# 04_-CPU_SIGNAL.net
KiCad netlist of a schematic drawn in Altium Designer
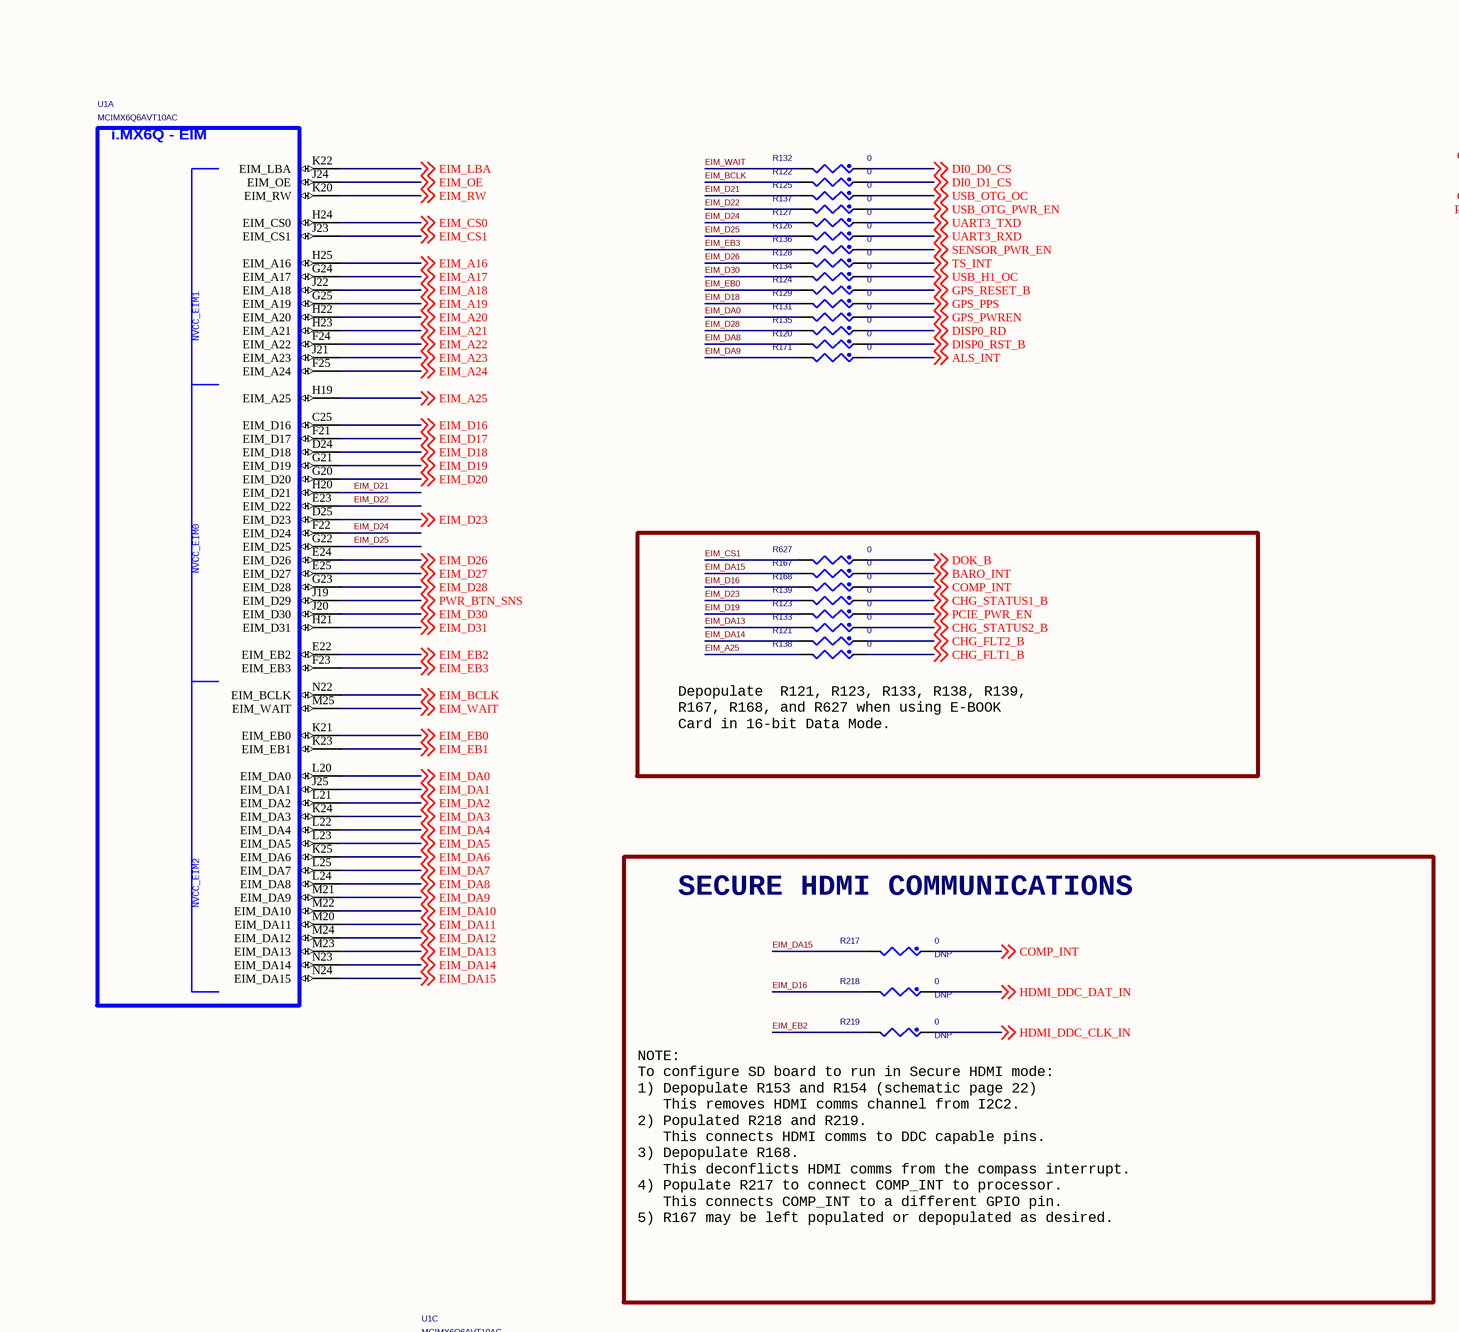
[diagram p0: [04]-CPU SIGNAL.SchDoc, top left]
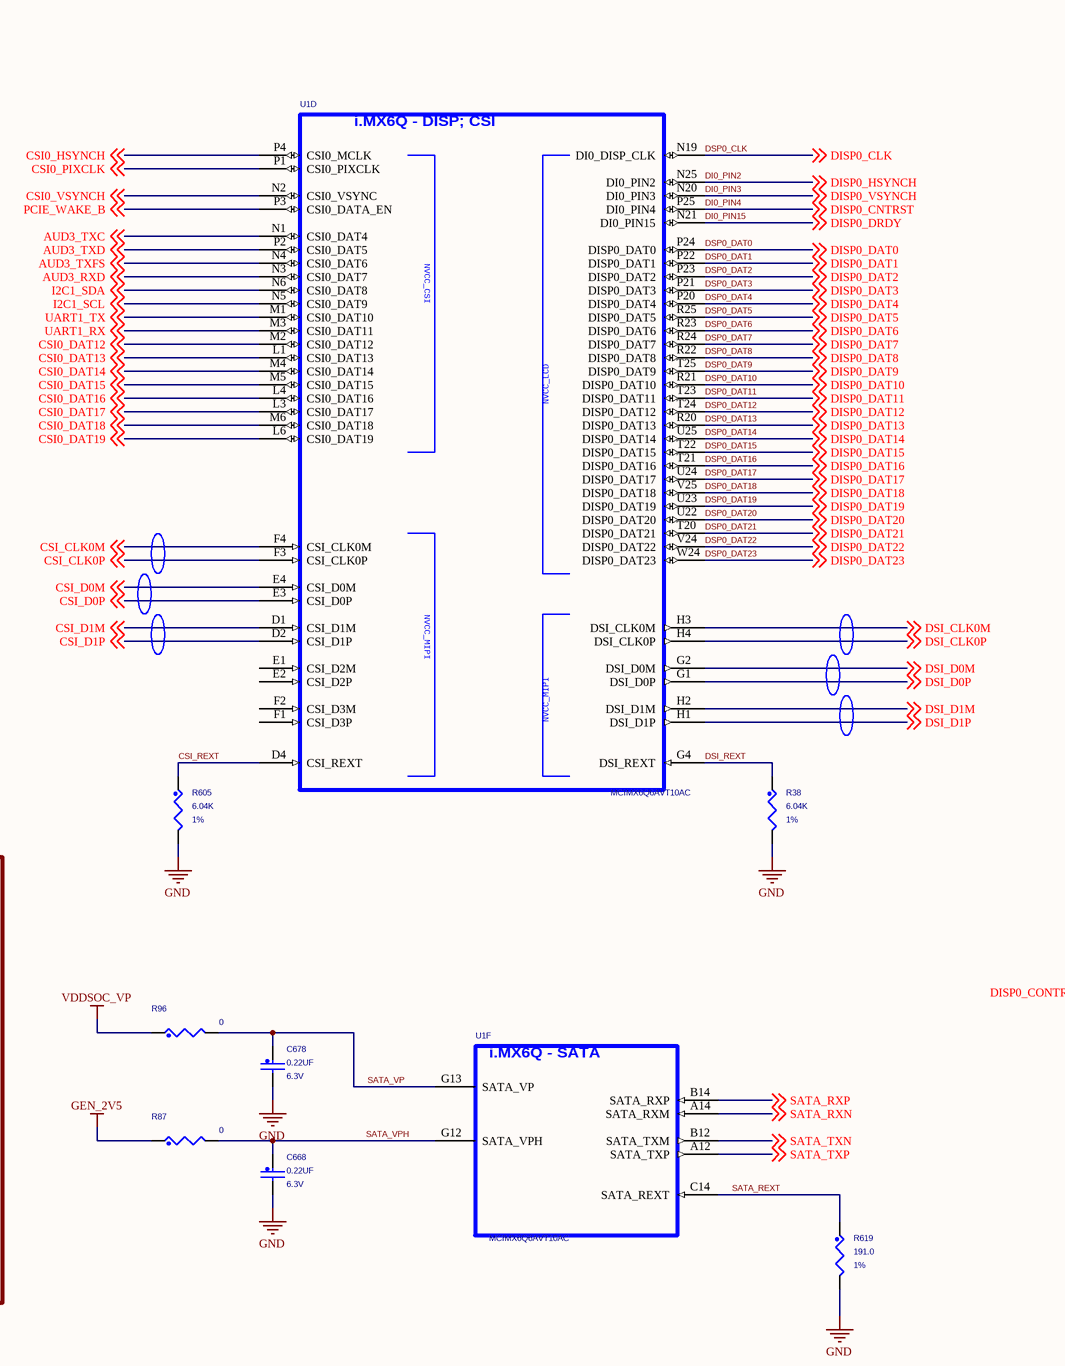
[diagram p1: [04]-CPU SIGNAL.SchDoc, top middle]
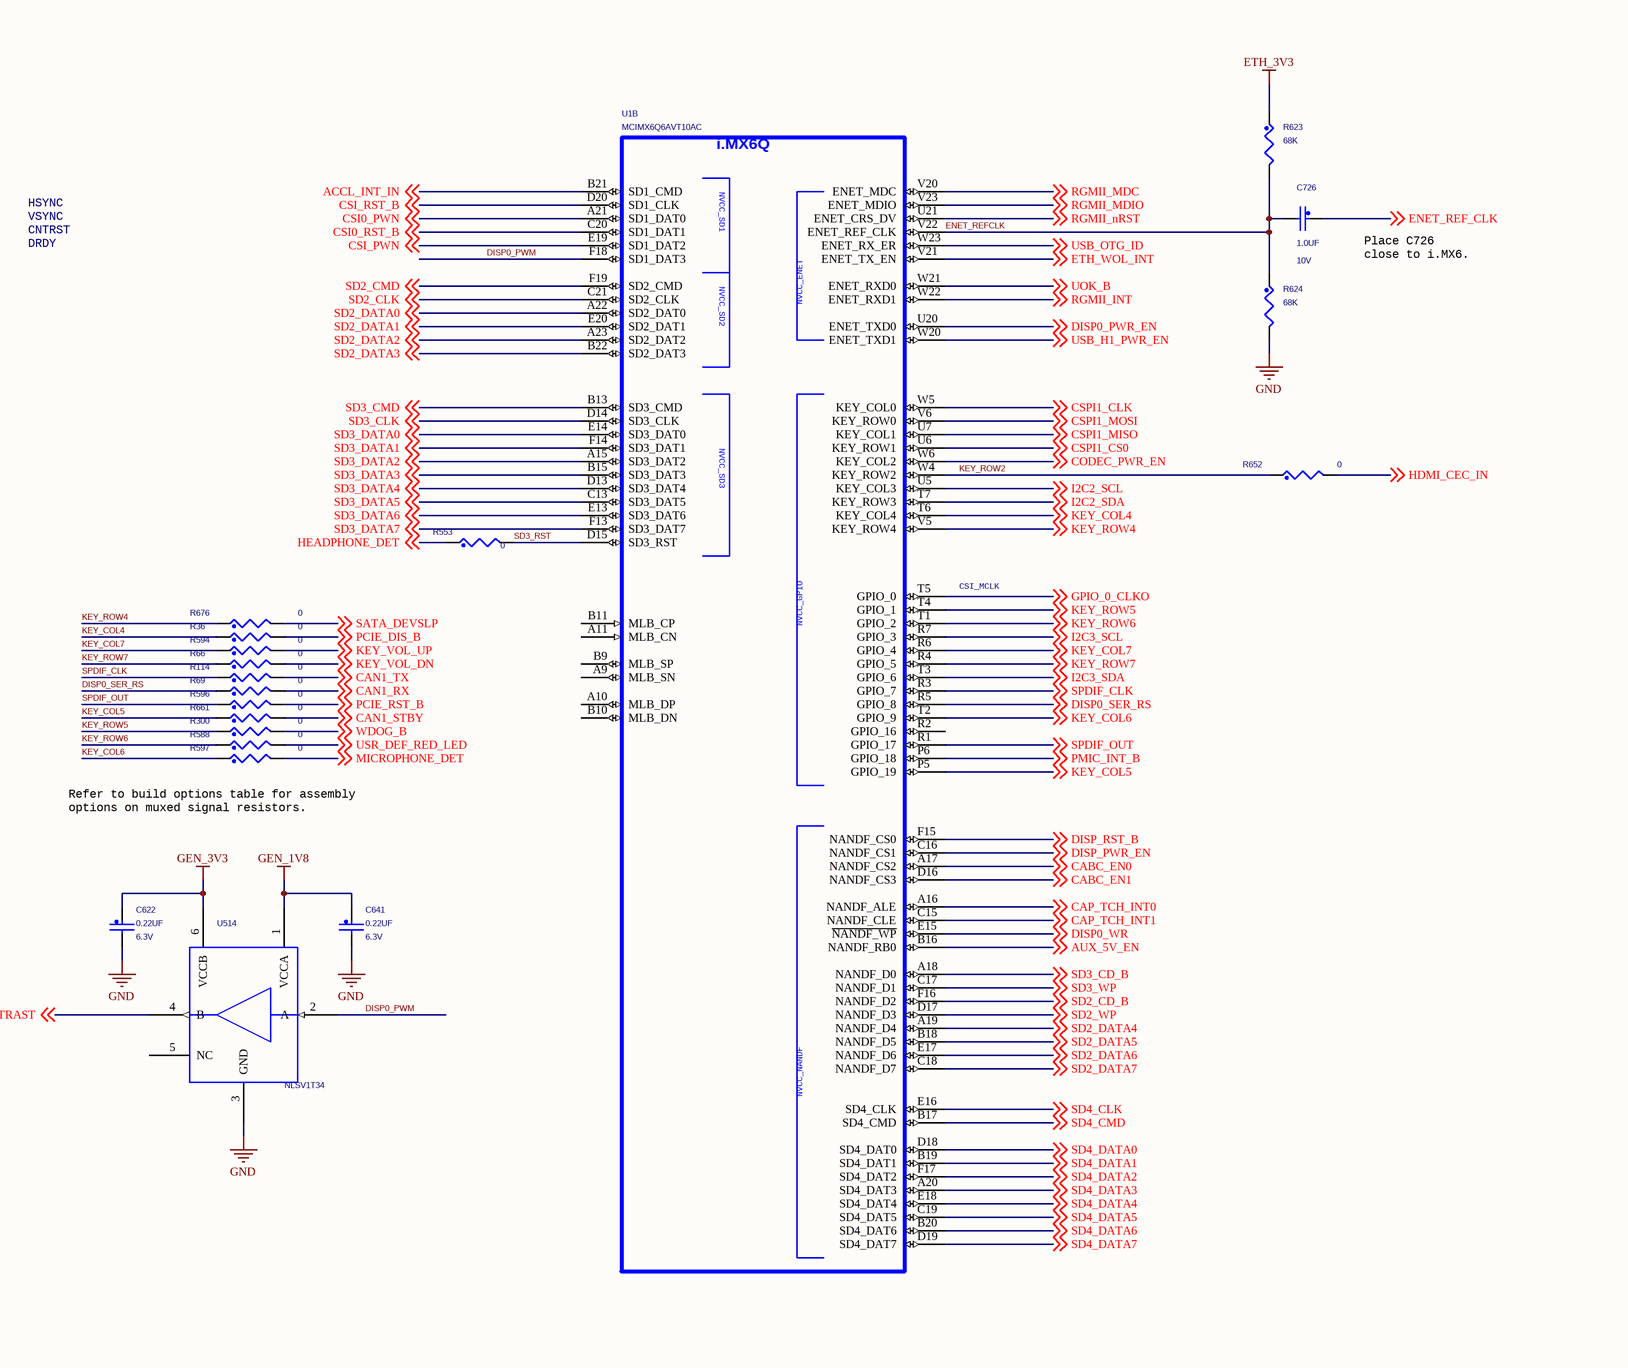
[diagram p2: [04]-CPU SIGNAL.SchDoc, top right]
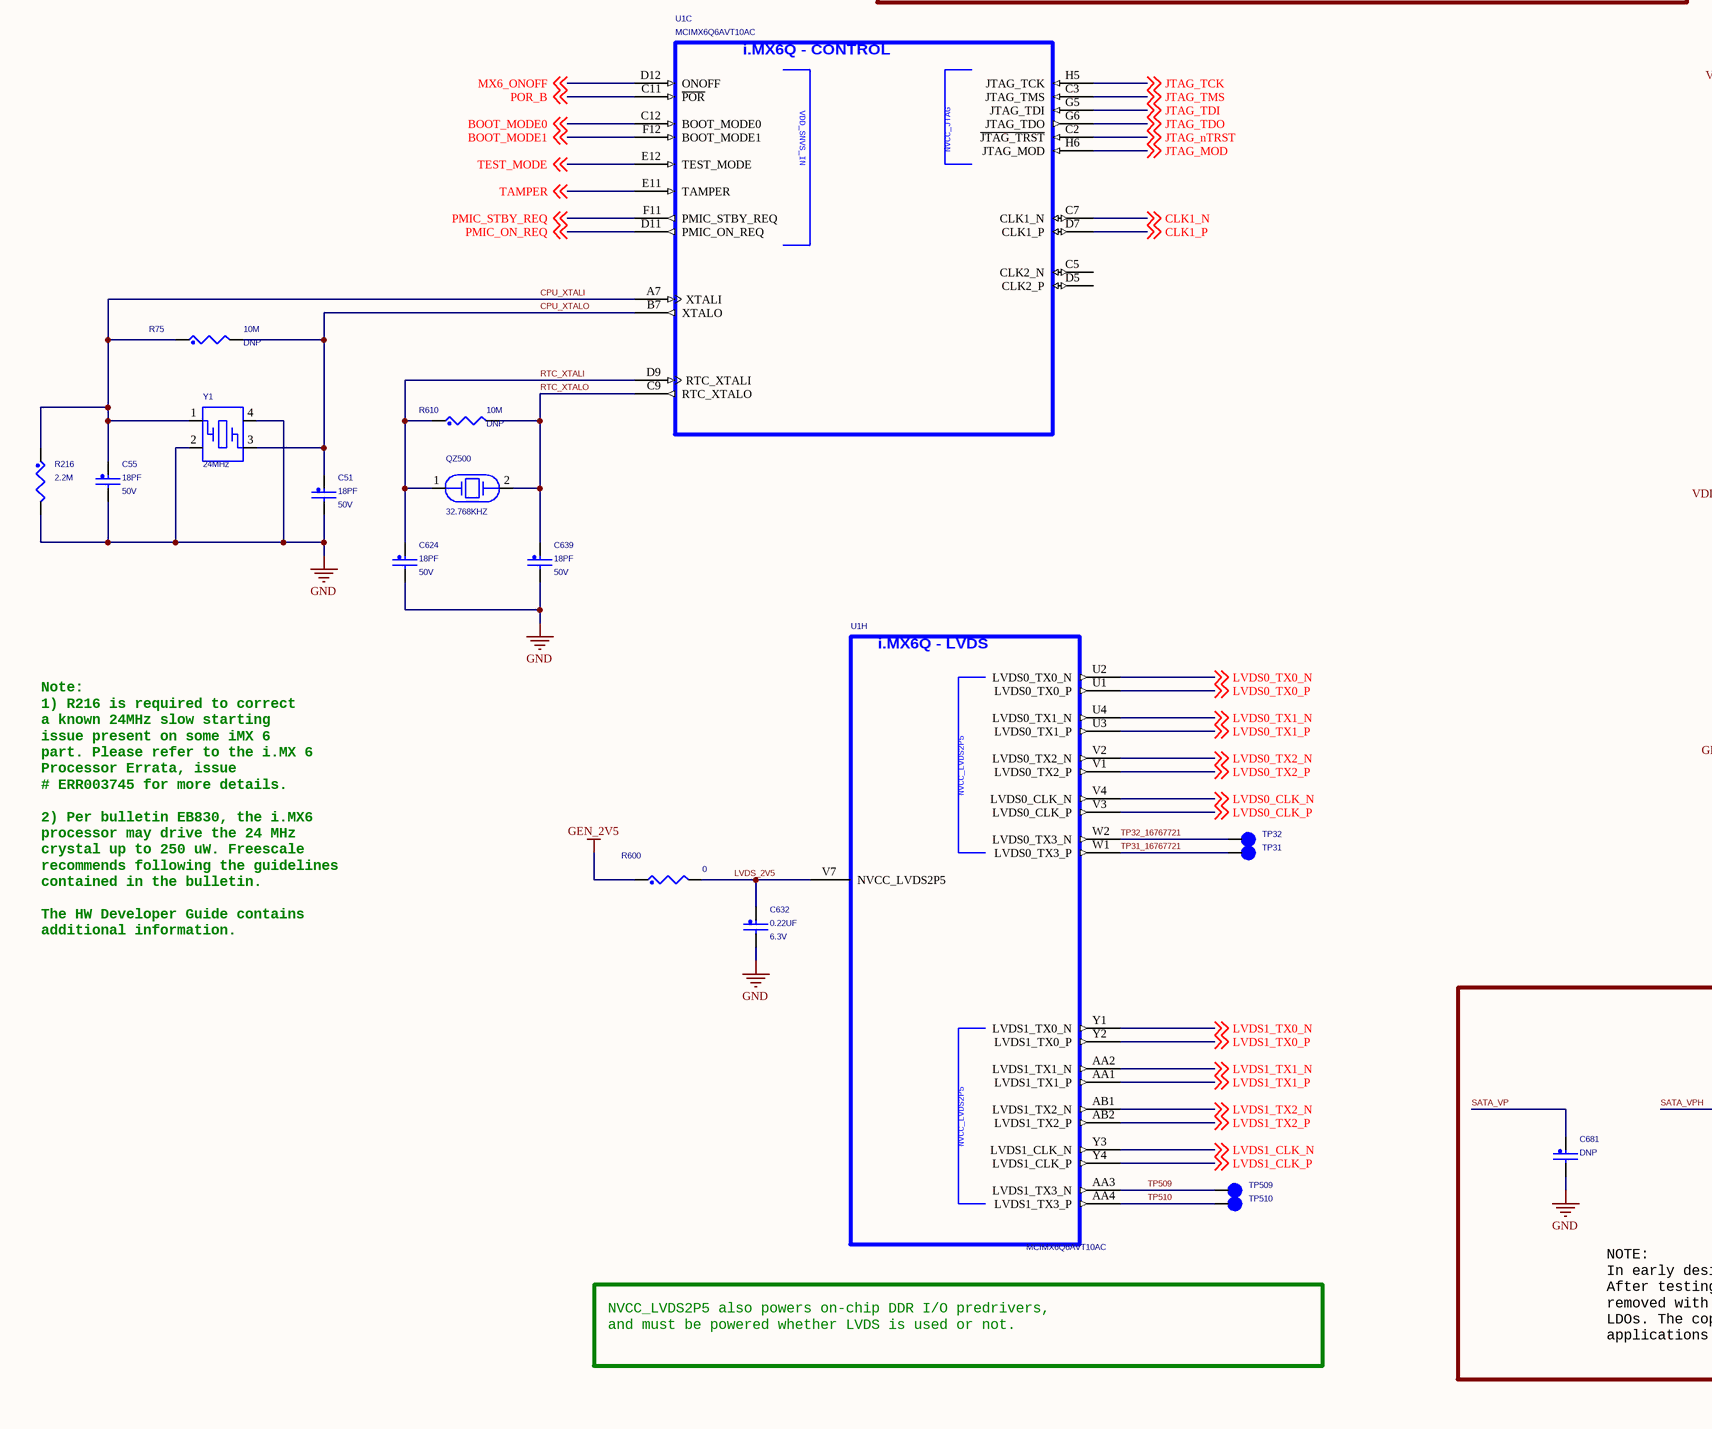
[diagram p3: [04]-CPU SIGNAL.SchDoc, bottom left]
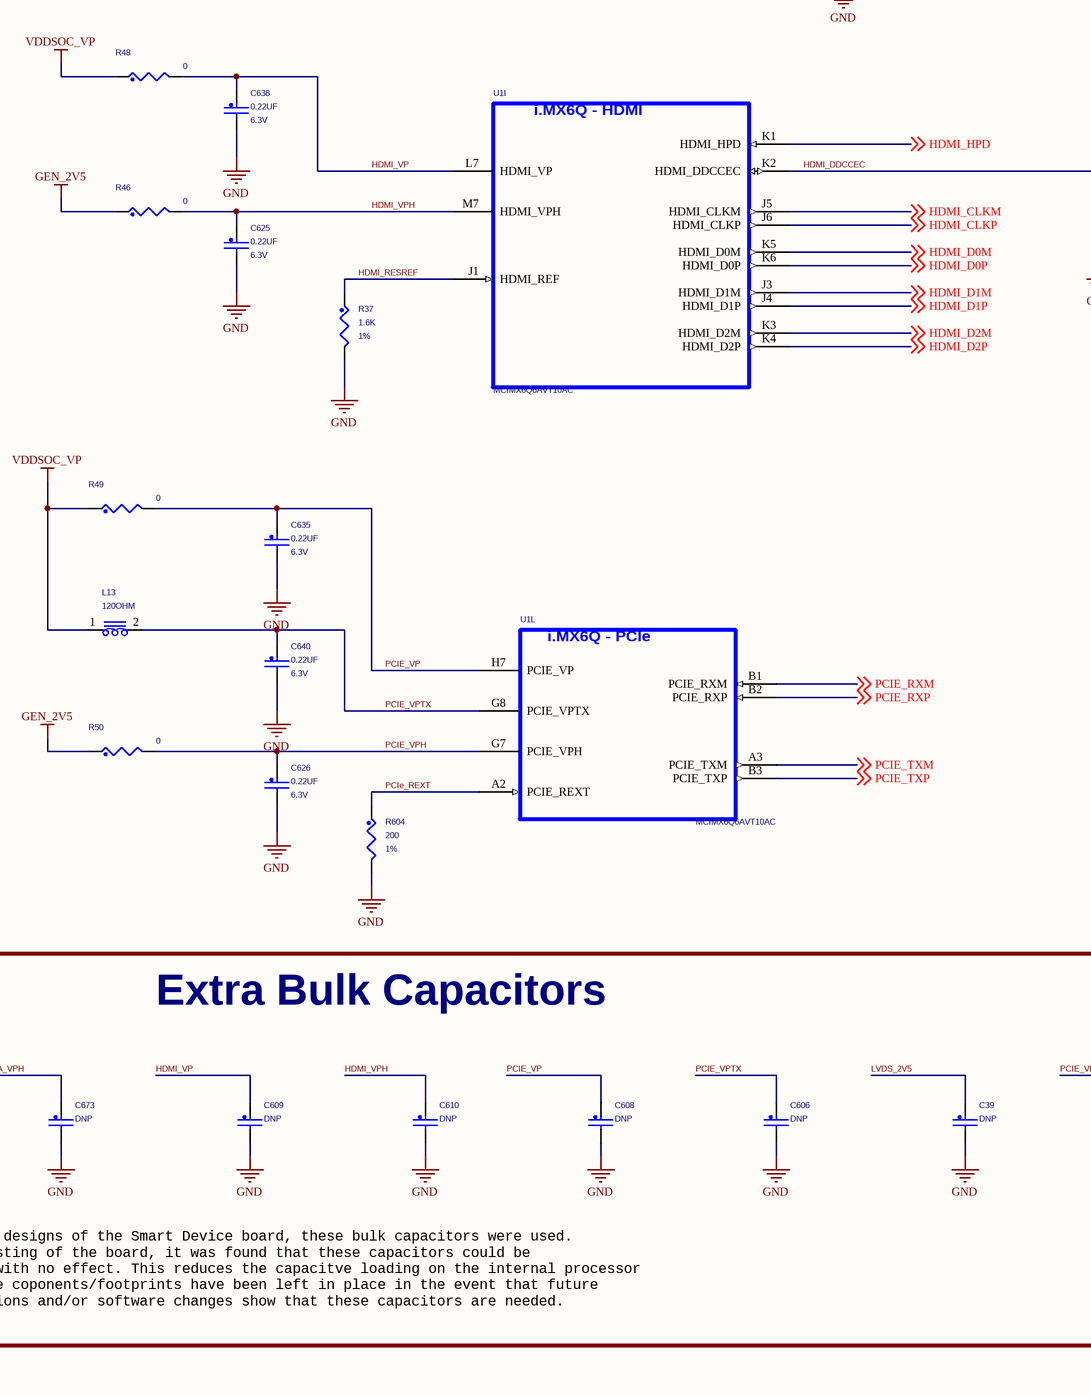
[diagram p4: [04]-CPU SIGNAL.SchDoc, bottom middle]
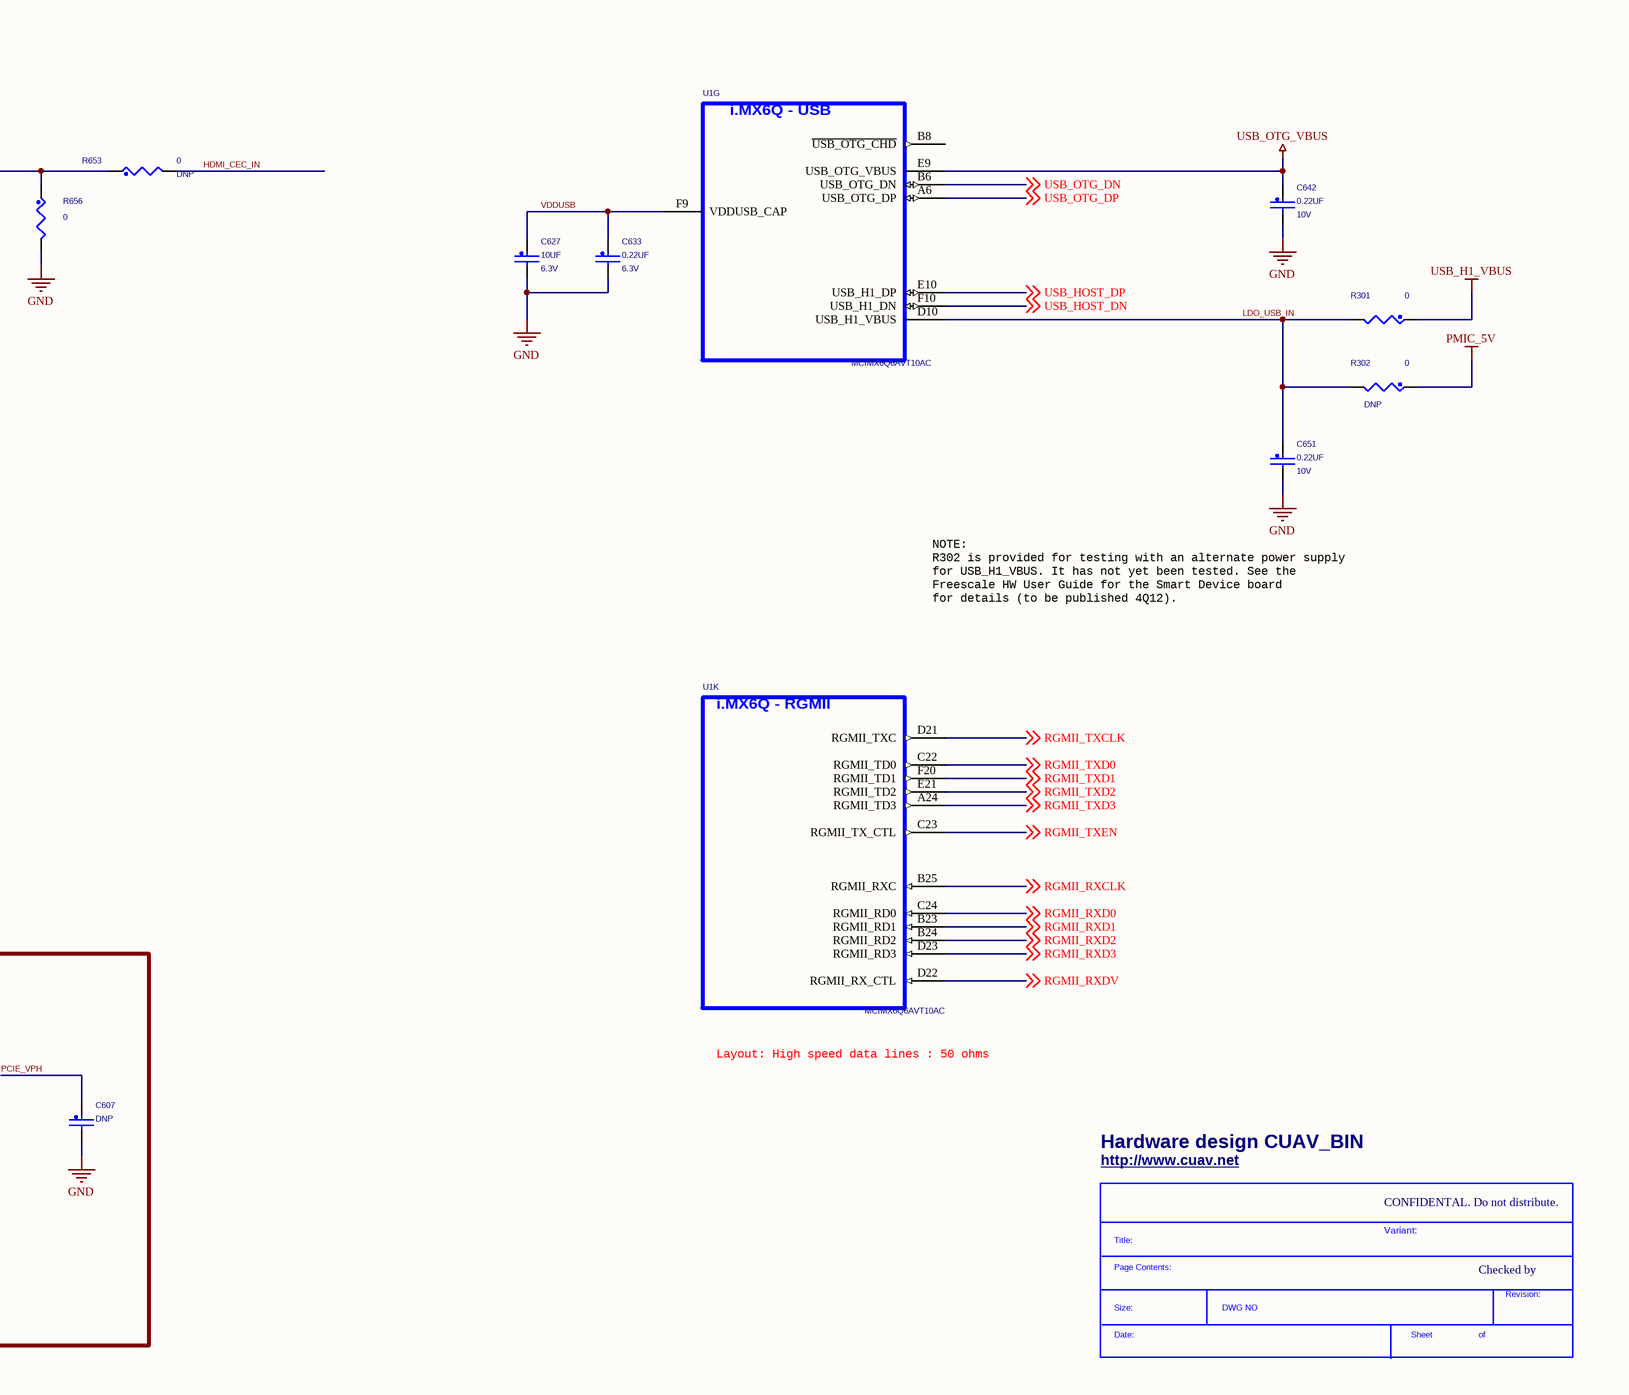
[diagram p5: [04]-CPU SIGNAL.SchDoc, bottom right]

(export (version "E")
  (design (tool "Eeschema 10.0.6"))
  (components
    (comp (ref "*") (value "SDTitleBlock") (libsource (lib "*") (part "SDTitleBlock")))
    (comp (ref "C39")
      (value "4.7UF")
      (description "CAP CER 4.7UF 10V 10% X5R 0603")
      (fields (field (name "TOLERANCE") "10%") (field (name "ASSY_OPT") "DNP") (field (name "VOLTAGE") "10V"))
      (libsource (lib "*") (part "CAP_NP"))
    )
    (comp (ref "C51")
      (value "18PF")
      (description "CAP CER 18PF 50V 1% C0G 0402")
      (fields (field (name "VOLTAGE") "50V") (field (name "TOLERANCE") "1%"))
      (libsource (lib "*") (part "CAP_NP"))
    )
    (comp (ref "C55")
      (value "18PF")
      (description "CAP CER 18PF 50V 1% C0G 0402")
      (fields (field (name "VOLTAGE") "50V") (field (name "TOLERANCE") "1%"))
      (libsource (lib "*") (part "CAP_NP"))
    )
    (comp (ref "C606")
      (value "4.7UF")
      (description "CAP CER 4.7UF 6.3V 10% X5R 0603")
      (fields
        (field (name "VOLTAGE") "6.3V")
        (field (name "TOLERANCE") "10%")
        (field (name "ASSY_OPT") "DNP")
      )
      (libsource (lib "*") (part "CAP_NP"))
    )
    (comp (ref "C607")
      (value "4.7UF")
      (description "CAP CER 4.7UF 6.3V 10% X5R 0603")
      (fields
        (field (name "VOLTAGE") "6.3V")
        (field (name "TOLERANCE") "10%")
        (field (name "ASSY_OPT") "DNP")
      )
      (libsource (lib "*") (part "CAP_NP"))
    )
    (comp (ref "C608")
      (value "4.7UF")
      (description "CAP CER 4.7UF 6.3V 10% X5R 0603")
      (fields
        (field (name "VOLTAGE") "6.3V")
        (field (name "TOLERANCE") "10%")
        (field (name "ASSY_OPT") "DNP")
      )
      (libsource (lib "*") (part "CAP_NP"))
    )
    (comp (ref "C609")
      (value "4.7UF")
      (description "CAP CER 4.7UF 6.3V 10% X5R 0603")
      (fields
        (field (name "TOLERANCE") "10%")
        (field (name "ASSY_OPT") "DNP")
        (field (name "VOLTAGE") "6.3V")
      )
      (libsource (lib "*") (part "CAP_NP"))
    )
    (comp (ref "C610")
      (value "4.7UF")
      (description "CAP CER 4.7UF 6.3V 10% X5R 0603")
      (fields
        (field (name "ASSY_OPT") "DNP")
        (field (name "TOLERANCE") "10%")
        (field (name "VOLTAGE") "6.3V")
      )
      (libsource (lib "*") (part "CAP_NP"))
    )
    (comp (ref "C622")
      (value "0.22UF")
      (description "CAP CER 0.22UF 6.3V 20% X5R 0201")
      (fields (field (name "TOLERANCE") "20%") (field (name "WVDC") "6.3V") (field (name "VOLTAGE") "6.3V"))
      (libsource (lib "*") (part "CAP_NP"))
    )
    (comp (ref "C624")
      (value "18PF")
      (description "CAP CER 18PF 50V 1% C0G 0402")
      (fields (field (name "VOLTAGE") "50V") (field (name "TOLERANCE") "1%"))
      (libsource (lib "*") (part "CAP_NP"))
    )
    (comp (ref "C625")
      (value "0.22UF")
      (description "CAP CER 0.22UF 6.3V 20% X5R 0201")
      (fields (field (name "WVDC") "6.3V") (field (name "TOLERANCE") "20%") (field (name "VOLTAGE") "6.3V"))
      (libsource (lib "*") (part "CAP_NP"))
    )
    (comp (ref "C626")
      (value "0.22UF")
      (description "CAP CER 0.22UF 6.3V 20% X5R 0201")
      (fields (field (name "VOLTAGE") "6.3V") (field (name "TOLERANCE") "20%") (field (name "WVDC") "6.3V"))
      (libsource (lib "*") (part "CAP_NP"))
    )
    (comp (ref "C627")
      (value "10UF")
      (description "CAP CER 10UF 6.3V 10% X5R 0603")
      (fields (field (name "TOLERANCE") "10%") (field (name "WVDC") "6.3V") (field (name "VOLTAGE") "6.3V"))
      (libsource (lib "*") (part "CAP_NP"))
    )
    (comp (ref "C632")
      (value "0.22UF")
      (description "CAP CER 0.22UF 6.3V 20% X5R 0201")
      (fields (field (name "VOLTAGE") "6.3V") (field (name "WVDC") "6.3V") (field (name "TOLERANCE") "20%"))
      (libsource (lib "*") (part "CAP_NP"))
    )
    (comp (ref "C633")
      (value "0.22UF")
      (description "CAP CER 0.22UF 6.3V 20% X5R 0201")
      (fields (field (name "WVDC") "6.3V") (field (name "TOLERANCE") "20%") (field (name "VOLTAGE") "6.3V"))
      (libsource (lib "*") (part "CAP_NP"))
    )
    (comp (ref "C635")
      (value "0.22UF")
      (description "CAP CER 0.22UF 6.3V 20% X5R 0201")
      (fields (field (name "VOLTAGE") "6.3V") (field (name "TOLERANCE") "20%") (field (name "WVDC") "6.3V"))
      (libsource (lib "*") (part "CAP_NP"))
    )
    (comp (ref "C638")
      (value "0.22UF")
      (description "CAP CER 0.22UF 6.3V 20% X5R 0201")
      (fields (field (name "WVDC") "6.3V") (field (name "TOLERANCE") "20%") (field (name "VOLTAGE") "6.3V"))
      (libsource (lib "*") (part "CAP_NP"))
    )
    (comp (ref "C639")
      (value "18PF")
      (description "CAP CER 18PF 50V 1% C0G 0402")
      (fields (field (name "VOLTAGE") "50V") (field (name "TOLERANCE") "1%"))
      (libsource (lib "*") (part "CAP_NP"))
    )
    (comp (ref "C640")
      (value "0.22UF")
      (description "CAP CER 0.22UF 6.3V 20% X5R 0201")
      (fields (field (name "VOLTAGE") "6.3V") (field (name "TOLERANCE") "20%") (field (name "WVDC") "6.3V"))
      (libsource (lib "*") (part "CAP_NP"))
    )
    (comp (ref "C641")
      (value "0.22UF")
      (description "CAP CER 0.22UF 6.3V 20% X5R 0201")
      (fields (field (name "VOLTAGE") "6.3V") (field (name "WVDC") "6.3V") (field (name "TOLERANCE") "20%"))
      (libsource (lib "*") (part "CAP_NP"))
    )
    (comp (ref "C642")
      (value "0.22UF")
      (description "CAP CER 0.22UF 10V 20% X5R 0201")
      (fields (field (name "WVDC") "10V") (field (name "TOLERANCE") "20%") (field (name "VOLTAGE") "10V"))
      (libsource (lib "*") (part "CAP_NP"))
    )
    (comp (ref "C651")
      (value "0.22UF")
      (description "CAP CER 0.22UF 10V 20% X5R 0201")
      (fields (field (name "WVDC") "10V") (field (name "TOLERANCE") "20%") (field (name "VOLTAGE") "10V"))
      (libsource (lib "*") (part "CAP_NP"))
    )
    (comp (ref "C668")
      (value "0.22UF")
      (description "CAP CER 0.22UF 6.3V 20% X5R 0201")
      (fields (field (name "TOLERANCE") "20%") (field (name "WVDC") "6.3V") (field (name "VOLTAGE") "6.3V"))
      (libsource (lib "*") (part "CAP_NP"))
    )
    (comp (ref "C673")
      (value "4.7UF")
      (description "CAP CER 4.7UF 6.3V 10% X5R 0603")
      (fields
        (field (name "VOLTAGE") "6.3V")
        (field (name "TOLERANCE") "10%")
        (field (name "ASSY_OPT") "DNP")
      )
      (libsource (lib "*") (part "CAP_NP"))
    )
    (comp (ref "C678")
      (value "0.22UF")
      (description "CAP CER 0.22UF 6.3V 20% X5R 0201")
      (fields (field (name "TOLERANCE") "20%") (field (name "WVDC") "6.3V") (field (name "VOLTAGE") "6.3V"))
      (libsource (lib "*") (part "CAP_NP"))
    )
    (comp (ref "C681")
      (value "4.7UF")
      (description "CAP CER 4.7UF 6.3V 10% X5R 0603")
      (fields
        (field (name "VOLTAGE") "6.3V")
        (field (name "TOLERANCE") "10%")
        (field (name "ASSY_OPT") "DNP")
      )
      (libsource (lib "*") (part "CAP_NP"))
    )
    (comp (ref "C726")
      (value "1.0UF")
      (description "CAP CER 1.0UF 10V 10% X5R 0402")
      (fields (field (name "WVDC") "10V"))
      (libsource (lib "*") (part "CAP_NP"))
    )
    (comp (ref "L13")
      (value "120OHM")
      (description "IND FER BEAD 120OHM@100MHZ 2A 25% 0603")
      (fields (field (name "TOLERANCE") "25%"))
      (libsource (lib "*") (part "BEAD_0"))
    )
    (comp (ref "QZ500")
      (value "32.768KHZ")
      (description "XTAL 32.768KHZ 12.5PF 20PPM 3.2X1.5MM SMT")
      (libsource (lib "*") (part "XTAL"))
    )
    (comp (ref "R36")
      (value "0")
      (description "RES MF ZERO OHM 1/10W -- 0402")
      (libsource (lib "*") (part "RES"))
    )
    (comp (ref "R37")
      (value "1.6K")
      (description "RES MF 1.6K  1/16W 1% 0402")
      (fields (field (name "TOLERANCE") "1%"))
      (libsource (lib "*") (part "RES"))
    )
    (comp (ref "R38")
      (value "6.04K")
      (description "RES MF 6.04K  1/16W 1% 0402")
      (fields (field (name "TOLERANCE") "1%"))
      (libsource (lib "*") (part "RES"))
    )
    (comp (ref "R46")
      (value "0")
      (description "RES MF ZERO OHM 1/10W -- 0402")
      (libsource (lib "*") (part "RES"))
    )
    (comp (ref "R48")
      (value "0")
      (description "RES MF ZERO OHM 1/10W -- 0402")
      (libsource (lib "*") (part "RES"))
    )
    (comp (ref "R49")
      (value "0")
      (description "RES MF ZERO OHM 1/10W -- 0402")
      (libsource (lib "*") (part "RES"))
    )
    (comp (ref "R50")
      (value "0")
      (description "RES MF ZERO OHM 1/10W -- 0402")
      (libsource (lib "*") (part "RES"))
    )
    (comp (ref "R66")
      (value "0")
      (description "RES MF ZERO OHM 1/10W -- 0402")
      (libsource (lib "*") (part "RES"))
    )
    (comp (ref "R69")
      (value "0")
      (description "RES MF ZERO OHM 1/10W -- 0402")
      (libsource (lib "*") (part "RES"))
    )
    (comp (ref "R75")
      (value "10M")
      (description "RES MF 10M 1/16W 1% 0402")
      (fields (field (name "ASSY_OPT") "DNP") (field (name "TOLERANCE") "1%"))
      (libsource (lib "*") (part "RES"))
    )
    (comp (ref "R87")
      (value "0")
      (description "RES MF ZERO OHM 1/10W -- 0402")
      (libsource (lib "*") (part "RES"))
    )
    (comp (ref "R96")
      (value "0")
      (description "RES MF ZERO OHM 1/10W -- 0402")
      (libsource (lib "*") (part "RES"))
    )
    (comp (ref "R114")
      (value "0")
      (description "RES MF ZERO OHM 1/10W -- 0402")
      (libsource (lib "*") (part "RES"))
    )
    (comp (ref "R120")
      (value "0")
      (description "RES MF ZERO OHM 1/10W -- 0402")
      (libsource (lib "*") (part "RES"))
    )
    (comp (ref "R121")
      (value "0")
      (description "RES MF ZERO OHM 1/10W -- 0402")
      (libsource (lib "*") (part "RES"))
    )
    (comp (ref "R122")
      (value "0")
      (description "RES MF ZERO OHM 1/10W -- 0402")
      (libsource (lib "*") (part "RES"))
    )
    (comp (ref "R123")
      (value "0")
      (description "RES MF ZERO OHM 1/10W -- 0402")
      (libsource (lib "*") (part "RES"))
    )
    (comp (ref "R124")
      (value "0")
      (description "RES MF ZERO OHM 1/10W -- 0402")
      (libsource (lib "*") (part "RES"))
    )
    (comp (ref "R125")
      (value "0")
      (description "RES MF ZERO OHM 1/10W -- 0402")
      (libsource (lib "*") (part "RES"))
    )
    (comp (ref "R126")
      (value "0")
      (description "RES MF ZERO OHM 1/10W -- 0402")
      (libsource (lib "*") (part "RES"))
    )
    (comp (ref "R127")
      (value "0")
      (description "RES MF ZERO OHM 1/10W -- 0402")
      (libsource (lib "*") (part "RES"))
    )
    (comp (ref "R128")
      (value "0")
      (description "RES MF ZERO OHM 1/10W -- 0402")
      (libsource (lib "*") (part "RES"))
    )
    (comp (ref "R129")
      (value "0")
      (description "RES MF ZERO OHM 1/10W -- 0402")
      (libsource (lib "*") (part "RES"))
    )
    (comp (ref "R131")
      (value "0")
      (description "RES MF ZERO OHM 1/10W -- 0402")
      (libsource (lib "*") (part "RES"))
    )
    (comp (ref "R132")
      (value "0")
      (description "RES MF ZERO OHM 1/10W -- 0402")
      (libsource (lib "*") (part "RES"))
    )
    (comp (ref "R133")
      (value "0")
      (description "RES MF ZERO OHM 1/10W -- 0402")
      (libsource (lib "*") (part "RES"))
    )
    (comp (ref "R134")
      (value "0")
      (description "RES MF ZERO OHM 1/10W -- 0402")
      (libsource (lib "*") (part "RES"))
    )
    (comp (ref "R135")
      (value "0")
      (description "RES MF ZERO OHM 1/10W -- 0402")
      (libsource (lib "*") (part "RES"))
    )
    (comp (ref "R136")
      (value "0")
      (description "RES MF ZERO OHM 1/10W -- 0402")
      (libsource (lib "*") (part "RES"))
    )
    (comp (ref "R137")
      (value "0")
      (description "RES MF ZERO OHM 1/10W -- 0402")
      (libsource (lib "*") (part "RES"))
    )
    (comp (ref "R138")
      (value "0")
      (description "RES MF ZERO OHM 1/10W -- 0402")
      (libsource (lib "*") (part "RES"))
    )
    (comp (ref "R139")
      (value "0")
      (description "RES MF ZERO OHM 1/10W -- 0402")
      (libsource (lib "*") (part "RES"))
    )
    (comp (ref "R167")
      (value "0")
      (description "RES MF ZERO OHM 1/10W -- 0402")
      (libsource (lib "*") (part "RES"))
    )
    (comp (ref "R168")
      (value "0")
      (description "RES MF ZERO OHM 1/10W -- 0402")
      (libsource (lib "*") (part "RES"))
    )
    (comp (ref "R171")
      (value "0")
      (description "RES MF ZERO OHM 1/10W -- 0402")
      (libsource (lib "*") (part "RES"))
    )
    (comp (ref "R216")
      (value "2.2M")
      (description "RES MF 2.2M  1/16W 1% 0402")
      (fields (field (name "TOLERANCE") "1%"))
      (libsource (lib "*") (part "RES"))
    )
    (comp (ref "R217")
      (value "0")
      (description "RES MF ZERO OHM 1/10W -- 0402")
      (fields (field (name "ASSY_OPT") "DNP"))
      (libsource (lib "*") (part "RES"))
    )
    (comp (ref "R218")
      (value "0")
      (description "RES MF ZERO OHM 1/10W -- 0402")
      (fields (field (name "ASSY_OPT") "DNP"))
      (libsource (lib "*") (part "RES"))
    )
    (comp (ref "R219")
      (value "0")
      (description "RES MF ZERO OHM 1/10W -- 0402")
      (fields (field (name "ASSY_OPT") "DNP"))
      (libsource (lib "*") (part "RES"))
    )
    (comp (ref "R300")
      (value "0")
      (description "RES MF ZERO OHM 1/10W -- 0402")
      (libsource (lib "*") (part "RES"))
    )
    (comp (ref "R301")
      (value "0")
      (description "RES MF ZERO OHM 1/10W -- 0402")
      (libsource (lib "*") (part "RES"))
    )
    (comp (ref "R302")
      (value "0")
      (description "RES MF ZERO OHM 1/10W -- 0402")
      (fields (field (name "ASSY_OPT") "DNP"))
      (libsource (lib "*") (part "RES"))
    )
    (comp (ref "R553")
      (value "0")
      (description "RES MF ZERO OHM 1/10W -- 0402")
      (libsource (lib "*") (part "RES"))
    )
    (comp (ref "R588")
      (value "0")
      (description "RES MF ZERO OHM 1/10W -- 0402")
      (libsource (lib "*") (part "RES"))
    )
    (comp (ref "R594")
      (value "0")
      (description "RES MF ZERO OHM 1/10W -- 0402")
      (libsource (lib "*") (part "RES"))
    )
    (comp (ref "R596")
      (value "0")
      (description "RES MF ZERO OHM 1/10W -- 0402")
      (libsource (lib "*") (part "RES"))
    )
    (comp (ref "R597")
      (value "0")
      (description "RES MF ZERO OHM 1/10W -- 0402")
      (libsource (lib "*") (part "RES"))
    )
    (comp (ref "R600")
      (value "0")
      (description "RES MF ZERO OHM 1/10W -- 0402")
      (libsource (lib "*") (part "RES"))
    )
    (comp (ref "R604")
      (value "200")
      (description "RES MF 200 OHM 1/16W 1% 0402")
      (fields (field (name "TOLERANCE") "1%"))
      (libsource (lib "*") (part "RES"))
    )
    (comp (ref "R605")
      (value "6.04K")
      (description "RES MF 6.04K  1/16W 1% 0402")
      (fields (field (name "TOLERANCE") "1%"))
      (libsource (lib "*") (part "RES"))
    )
    (comp (ref "R610")
      (value "10M")
      (description "RES MF 10M 1/16W 1% 0402")
      (fields (field (name "ASSY_OPT") "DNP") (field (name "TOLERANCE") "1%"))
      (libsource (lib "*") (part "RES"))
    )
    (comp (ref "R619")
      (value "191.0")
      (description "RES MF 191.0 OHM  1/10W 1% 0603")
      (fields (field (name "TOLERANCE") "1%"))
      (libsource (lib "*") (part "RES"))
    )
    (comp (ref "R623")
      (value "68K")
      (description "RES MF 68K  1/16W 1% 0402")
      (fields (field (name "TOLERANCE") "1%"))
      (libsource (lib "*") (part "RES"))
    )
    (comp (ref "R624")
      (value "68K")
      (description "RES MF 68K  1/16W 1% 0402")
      (fields (field (name "TOLERANCE") "1%"))
      (libsource (lib "*") (part "RES"))
    )
    (comp (ref "R627")
      (value "0")
      (description "RES MF ZERO OHM 1/10W -- 0402")
      (libsource (lib "*") (part "RES"))
    )
    (comp (ref "R652")
      (value "0")
      (description "RES MF ZERO OHM 1/10W -- 0402")
      (libsource (lib "*") (part "RES"))
    )
    (comp (ref "R653")
      (value "0")
      (description "RES MF ZERO OHM 1/10W -- 0402")
      (fields (field (name "ASSY_OPT") "DNP"))
      (libsource (lib "*") (part "RES"))
    )
    (comp (ref "R656")
      (value "0")
      (description "RES MF ZERO OHM 1/10W -- 0402")
      (libsource (lib "*") (part "RES"))
    )
    (comp (ref "R661")
      (value "0")
      (description "RES MF ZERO OHM 1/10W -- 0402")
      (libsource (lib "*") (part "RES"))
    )
    (comp (ref "R676")
      (value "0")
      (description "RES MF ZERO OHM 1/10W -- 0402")
      (libsource (lib "*") (part "RES"))
    )
    (comp (ref "TP31")
      (value "tpad_020")
      (description "TEST POINT PAD 0.5MM DIA SMT, NO PART TO ORDER")
      (libsource (lib "*") (part "TESTLOOP"))
    )
    (comp (ref "TP32")
      (value "tpad_020")
      (description "TEST POINT PAD 0.5MM DIA SMT, NO PART TO ORDER")
      (libsource (lib "*") (part "TESTLOOP"))
    )
    (comp (ref "TP509")
      (value "tpad_020")
      (description "TEST POINT PAD 0.5MM DIA SMT, NO PART TO ORDER")
      (libsource (lib "*") (part "TESTLOOP"))
    )
    (comp (ref "TP510")
      (value "tpad_020")
      (description "TEST POINT PAD 0.5MM DIA SMT, NO PART TO ORDER")
      (libsource (lib "*") (part "TESTLOOP"))
    )
    (comp (ref "U1")
      (value "MCIMX6Q6AVT10AC")
      (description "IC MCU MX6QUAD ARM CORTEX-A9 FCPBGA624")
      (libsource (lib "*") (part "PCIMX6Q6VV1A"))
    )
    (comp (ref "U514")
      (value "NLSV1T34")
      (description "IC VXLTR 1 BIT DUAL-SUPPLY 0.9-4.5V 613AF")
      (libsource (lib "*") (part "NLSV1T34"))
    )
    (comp (ref "Y1")
      (value "24MHz")
      (description "XTAL 24MHZ -- 3.2X2.5MM SMT")
      (libsource (lib "*") (part "XTAL_13Y_A"))
    )
  )
  (nets
    (net (code "1") (name "/CPU_XTALI") (class "Default")
      (node (ref "C55") (pin "1") (pinfunction "1_1") (pintype "passive"))
      (node (ref "R216") (pin "1") (pinfunction "1_1") (pintype "passive"))
      (node (ref "R75") (pin "1") (pinfunction "1_1") (pintype "passive"))
      (node (ref "U1") (pin "A7") (pinfunction "XTALI_A7") (pintype "input"))
      (node (ref "Y1") (pin "1") (pinfunction "1_1") (pintype "passive"))
    )
    (net (code "2") (name "/CPU_XTALO") (class "Default")
      (node (ref "C51") (pin "1") (pinfunction "1_1") (pintype "passive"))
      (node (ref "R75") (pin "2") (pinfunction "2_2") (pintype "passive"))
      (node (ref "U1") (pin "B7") (pinfunction "XTALO_B7") (pintype "output"))
      (node (ref "Y1") (pin "3") (pinfunction "3_3") (pintype "passive"))
    )
    (net (code "3") (name "/CSI_REXT") (class "Default")
      (node (ref "R605") (pin "1") (pinfunction "1_1") (pintype "passive"))
      (node (ref "U1") (pin "D4") (pinfunction "CSI_REXT_D4") (pintype "input"))
    )
    (net (code "4") (name "/DISP0_PWM") (class "Default")
      (node (ref "U1") (pin "F18") (pinfunction "SD1_DAT3_F18") (pintype "bidirectional"))
      (node (ref "U514") (pin "2") (pinfunction "A_2") (pintype "input"))
    )
    (net (code "5") (name "/DSI_REXT") (class "Default")
      (node (ref "R38") (pin "1") (pinfunction "1_1") (pintype "passive"))
      (node (ref "U1") (pin "G4") (pinfunction "DSI_REXT_G4") (pintype "input"))
    )
    (net (code "6") (name "/EIM_D21") (class "Default")
      (node (ref "R125") (pin "2") (pinfunction "2_2") (pintype "passive"))
      (node (ref "U1") (pin "H20") (pinfunction "EIM_D21_H20") (pintype "bidirectional"))
    )
    (net (code "7") (name "/EIM_D22") (class "Default")
      (node (ref "R137") (pin "2") (pinfunction "2_2") (pintype "passive"))
      (node (ref "U1") (pin "E23") (pinfunction "EIM_D22_E23") (pintype "bidirectional"))
    )
    (net (code "8") (name "/EIM_D24") (class "Default")
      (node (ref "R127") (pin "2") (pinfunction "2_2") (pintype "passive"))
      (node (ref "U1") (pin "F22") (pinfunction "EIM_D24_F22") (pintype "bidirectional"))
    )
    (net (code "9") (name "/EIM_D25") (class "Default")
      (node (ref "R126") (pin "2") (pinfunction "2_2") (pintype "passive"))
      (node (ref "U1") (pin "G22") (pinfunction "EIM_D25_G22") (pintype "bidirectional"))
    )
    (net (code "10") (name "/ENET_REFCLK") (class "Default")
      (node (ref "C726") (pin "2") (pinfunction "2_2") (pintype "passive"))
      (node (ref "R623") (pin "2") (pinfunction "2_2") (pintype "passive"))
      (node (ref "R624") (pin "1") (pinfunction "1_1") (pintype "passive"))
      (node (ref "U1") (pin "V22") (pinfunction "ENET_REF_CLK_V22") (pintype "bidirectional"))
    )
    (net (code "11") (name "/HDMI_DDCCEC") (class "Default")
      (node (ref "R653") (pin "1") (pinfunction "1_1") (pintype "passive"))
      (node (ref "R656") (pin "1") (pinfunction "1_1") (pintype "passive"))
      (node (ref "U1") (pin "K2") (pinfunction "HDMI_DDCCEC_K2") (pintype "bidirectional"))
    )
    (net (code "12") (name "/HDMI_RESREF") (class "Default")
      (node (ref "R37") (pin "1") (pinfunction "1_1") (pintype "passive"))
      (node (ref "U1") (pin "J1") (pinfunction "HDMI_REF_J1") (pintype "input"))
    )
    (net (code "13") (name "/HDMI_VP") (class "Default")
      (node (ref "C609") (pin "1") (pinfunction "1_1") (pintype "passive"))
      (node (ref "C638") (pin "1") (pinfunction "1_1") (pintype "passive"))
      (node (ref "R48") (pin "2") (pinfunction "2_2") (pintype "passive"))
      (node (ref "U1") (pin "L7") (pinfunction "HDMI_VP_L7") (pintype "power_in"))
    )
    (net (code "14") (name "/HDMI_VPH") (class "Default")
      (node (ref "C610") (pin "1") (pinfunction "1_1") (pintype "passive"))
      (node (ref "C625") (pin "1") (pinfunction "1_1") (pintype "passive"))
      (node (ref "R46") (pin "2") (pinfunction "2_2") (pintype "passive"))
      (node (ref "U1") (pin "M7") (pinfunction "HDMI_VPH_M7") (pintype "power_in"))
    )
    (net (code "15") (name "/KEY_ROW2") (class "Default")
      (node (ref "R652") (pin "1") (pinfunction "1_1") (pintype "passive"))
      (node (ref "U1") (pin "W4") (pinfunction "KEY_ROW2_W4") (pintype "bidirectional"))
    )
    (net (code "16") (name "/LDO_USB_IN") (class "Default")
      (node (ref "C651") (pin "1") (pinfunction "1_1") (pintype "passive"))
      (node (ref "R301") (pin "2") (pinfunction "2_2") (pintype "passive"))
      (node (ref "R302") (pin "2") (pinfunction "2_2") (pintype "passive"))
      (node (ref "U1") (pin "D10") (pinfunction "USB_H1_VBUS_D10") (pintype "power_in"))
    )
    (net (code "17") (name "/LVDS_2V5") (class "Default")
      (node (ref "C39") (pin "1") (pinfunction "1_1") (pintype "passive"))
      (node (ref "C632") (pin "1") (pinfunction "1_1") (pintype "passive"))
      (node (ref "R600") (pin "2") (pinfunction "2_2") (pintype "passive"))
      (node (ref "U1") (pin "V7") (pinfunction "NVCC_LVDS2P5_V7") (pintype "power_in"))
    )
    (net (code "18") (name "/PCIE_VP") (class "Default")
      (node (ref "C608") (pin "1") (pinfunction "1_1") (pintype "passive"))
      (node (ref "C635") (pin "1") (pinfunction "1_1") (pintype "passive"))
      (node (ref "R49") (pin "2") (pinfunction "2_2") (pintype "passive"))
      (node (ref "U1") (pin "H7") (pinfunction "PCIE_VP_H7") (pintype "power_in"))
    )
    (net (code "19") (name "/PCIE_VPH") (class "Default")
      (node (ref "C607") (pin "1") (pinfunction "1_1") (pintype "passive"))
      (node (ref "C626") (pin "1") (pinfunction "1_1") (pintype "passive"))
      (node (ref "R50") (pin "2") (pinfunction "2_2") (pintype "passive"))
      (node (ref "U1") (pin "G7") (pinfunction "PCIE_VPH_G7") (pintype "power_in"))
    )
    (net (code "20") (name "/PCIE_VPTX") (class "Default")
      (node (ref "C606") (pin "1") (pinfunction "1_1") (pintype "passive"))
      (node (ref "C640") (pin "1") (pinfunction "1_1") (pintype "passive"))
      (node (ref "L13") (pin "2") (pinfunction "2_2") (pintype "passive"))
      (node (ref "U1") (pin "G8") (pinfunction "PCIE_VPTX_G8") (pintype "power_in"))
    )
    (net (code "21") (name "/PCIe_REXT") (class "Default")
      (node (ref "R604") (pin "1") (pinfunction "1_1") (pintype "passive"))
      (node (ref "U1") (pin "A2") (pinfunction "PCIE_REXT_A2") (pintype "input"))
    )
    (net (code "22") (name "/RTC_XTALI") (class "Default")
      (node (ref "C624") (pin "1") (pinfunction "1_1") (pintype "passive"))
      (node (ref "QZ500") (pin "1") (pinfunction "1_1") (pintype "passive"))
      (node (ref "R610") (pin "1") (pinfunction "1_1") (pintype "passive"))
      (node (ref "U1") (pin "D9") (pinfunction "RTC_XTALI_D9") (pintype "input"))
    )
    (net (code "23") (name "/RTC_XTALO") (class "Default")
      (node (ref "C639") (pin "1") (pinfunction "1_1") (pintype "passive"))
      (node (ref "QZ500") (pin "2") (pinfunction "2_2") (pintype "passive"))
      (node (ref "R610") (pin "2") (pinfunction "2_2") (pintype "passive"))
      (node (ref "U1") (pin "C9") (pinfunction "RTC_XTALO_C9") (pintype "output"))
    )
    (net (code "24") (name "/SATA_REXT") (class "Default")
      (node (ref "R619") (pin "1") (pinfunction "1_1") (pintype "passive"))
      (node (ref "U1") (pin "C14") (pinfunction "SATA_REXT_C14") (pintype "input"))
    )
    (net (code "25") (name "/SATA_VP") (class "Default")
      (node (ref "C678") (pin "1") (pinfunction "1_1") (pintype "passive"))
      (node (ref "C681") (pin "1") (pinfunction "1_1") (pintype "passive"))
      (node (ref "R96") (pin "2") (pinfunction "2_2") (pintype "passive"))
      (node (ref "U1") (pin "G13") (pinfunction "SATA_VP_G13") (pintype "power_in"))
    )
    (net (code "26") (name "/SATA_VPH") (class "Default")
      (node (ref "C668") (pin "1") (pinfunction "1_1") (pintype "passive"))
      (node (ref "C673") (pin "1") (pinfunction "1_1") (pintype "passive"))
      (node (ref "R87") (pin "2") (pinfunction "2_2") (pintype "passive"))
      (node (ref "U1") (pin "G12") (pinfunction "SATA_VPH_G12") (pintype "power_in"))
    )
    (net (code "27") (name "/SD3_RST") (class "Default")
      (node (ref "R553") (pin "2") (pinfunction "2_2") (pintype "passive"))
      (node (ref "U1") (pin "D15") (pinfunction "SD3_RST_D15") (pintype "bidirectional"))
    )
    (net (code "28") (name "/TP31_16767721") (class "Default")
      (node (ref "TP31") (pin "1") (pinfunction "Pin1_1") (pintype "passive"))
      (node (ref "U1") (pin "W1") (pinfunction "LVDS0_TX3_P_W1") (pintype "output"))
    )
    (net (code "29") (name "/TP32_16767721") (class "Default")
      (node (ref "TP32") (pin "1") (pinfunction "Pin1_1") (pintype "passive"))
      (node (ref "U1") (pin "W2") (pinfunction "LVDS0_TX3_N_W2") (pintype "output"))
    )
    (net (code "30") (name "/TP509") (class "Default")
      (node (ref "TP509") (pin "1") (pinfunction "Pin1_1") (pintype "passive"))
      (node (ref "U1") (pin "AA3") (pinfunction "LVDS1_TX3_N_AA3") (pintype "output"))
    )
    (net (code "31") (name "/TP510") (class "Default")
      (node (ref "TP510") (pin "1") (pinfunction "Pin1_1") (pintype "passive"))
      (node (ref "U1") (pin "AA4") (pinfunction "LVDS1_TX3_P_AA4") (pintype "output"))
    )
    (net (code "32") (name "/VDDUSB") (class "Default")
      (node (ref "C627") (pin "1") (pinfunction "1_1") (pintype "passive"))
      (node (ref "C633") (pin "1") (pinfunction "1_1") (pintype "passive"))
      (node (ref "U1") (pin "F9") (pinfunction "VDDUSB_CAP_F9") (pintype "power_in"))
    )
    (net (code "33") (name "ACCL_INT_IN") (class "Default")
      (node (ref "U1") (pin "B21") (pinfunction "SD1_CMD_B21") (pintype "bidirectional"))
    )
    (net (code "34") (name "ALS_INT") (class "Default")
      (node (ref "R171") (pin "1") (pinfunction "1_1") (pintype "passive"))
    )
    (net (code "35") (name "AUD3_RXD") (class "Default")
      (node (ref "U1") (pin "N3") (pinfunction "CSI0_DAT7_N3") (pintype "bidirectional"))
    )
    (net (code "36") (name "AUD3_TXC") (class "Default")
      (node (ref "U1") (pin "N1") (pinfunction "CSI0_DAT4_N1") (pintype "bidirectional"))
    )
    (net (code "37") (name "AUD3_TXD") (class "Default")
      (node (ref "U1") (pin "P2") (pinfunction "CSI0_DAT5_P2") (pintype "bidirectional"))
    )
    (net (code "38") (name "AUD3_TXFS") (class "Default")
      (node (ref "U1") (pin "N4") (pinfunction "CSI0_DAT6_N4") (pintype "bidirectional"))
    )
    (net (code "39") (name "AUX_5V_EN") (class "Default")
      (node (ref "U1") (pin "B16") (pinfunction "NANDF_RB0_B16") (pintype "bidirectional"))
    )
    (net (code "40") (name "BARO_INT") (class "Default")
      (node (ref "R167") (pin "1") (pinfunction "1_1") (pintype "passive"))
    )
    (net (code "41") (name "BOOT_MODE0") (class "Default")
      (node (ref "U1") (pin "C12") (pinfunction "BOOT_MODE0_C12") (pintype "input"))
    )
    (net (code "42") (name "BOOT_MODE1") (class "Default")
      (node (ref "U1") (pin "F12") (pinfunction "BOOT_MODE1_F12") (pintype "input"))
    )
    (net (code "43") (name "CABC_EN0") (class "Default")
      (node (ref "U1") (pin "A17") (pinfunction "NANDF_CS2_A17") (pintype "bidirectional"))
    )
    (net (code "44") (name "CABC_EN1") (class "Default")
      (node (ref "U1") (pin "D16") (pinfunction "NANDF_CS3_D16") (pintype "bidirectional"))
    )
    (net (code "45") (name "CAN1_RX") (class "Default")
      (node (ref "R69") (pin "2") (pinfunction "2_2") (pintype "passive"))
    )
    (net (code "46") (name "CAN1_STBY") (class "Default")
      (node (ref "R661") (pin "2") (pinfunction "2_2") (pintype "passive"))
    )
    (net (code "47") (name "CAN1_TX") (class "Default")
      (node (ref "R114") (pin "2") (pinfunction "2_2") (pintype "passive"))
    )
    (net (code "48") (name "CAP_TCH_INT0") (class "Default")
      (node (ref "U1") (pin "A16") (pinfunction "NANDF_ALE_A16") (pintype "bidirectional"))
    )
    (net (code "49") (name "CAP_TCH_INT1") (class "Default")
      (node (ref "U1") (pin "C15") (pinfunction "NANDF_CLE_C15") (pintype "bidirectional"))
    )
    (net (code "50") (name "CHG_FLT1_B") (class "Default")
      (node (ref "R138") (pin "1") (pinfunction "1_1") (pintype "passive"))
    )
    (net (code "51") (name "CHG_FLT2_B") (class "Default")
      (node (ref "R121") (pin "1") (pinfunction "1_1") (pintype "passive"))
    )
    (net (code "52") (name "CHG_STATUS1_B") (class "Default")
      (node (ref "R139") (pin "1") (pinfunction "1_1") (pintype "passive"))
    )
    (net (code "53") (name "CHG_STATUS2_B") (class "Default")
      (node (ref "R133") (pin "1") (pinfunction "1_1") (pintype "passive"))
    )
    (net (code "54") (name "CLK1_N") (class "Default")
      (node (ref "U1") (pin "C7") (pinfunction "CLK1_N_C7") (pintype "bidirectional"))
    )
    (net (code "55") (name "CLK1_P") (class "Default")
      (node (ref "U1") (pin "D7") (pinfunction "CLK1_P_D7") (pintype "bidirectional"))
    )
    (net (code "56") (name "CODEC_PWR_EN") (class "Default")
      (node (ref "U1") (pin "W6") (pinfunction "KEY_COL2_W6") (pintype "bidirectional"))
    )
    (net (code "57") (name "COMP_INT") (class "Default")
      (node (ref "R168") (pin "1") (pinfunction "1_1") (pintype "passive"))
      (node (ref "R217") (pin "1") (pinfunction "1_1") (pintype "passive"))
    )
    (net (code "58") (name "CSI0_DAT12") (class "Default")
      (node (ref "U1") (pin "M2") (pinfunction "CSI0_DAT12_M2") (pintype "bidirectional"))
    )
    (net (code "59") (name "CSI0_DAT13") (class "Default")
      (node (ref "U1") (pin "L1") (pinfunction "CSI0_DAT13_L1") (pintype "bidirectional"))
    )
    (net (code "60") (name "CSI0_DAT14") (class "Default")
      (node (ref "U1") (pin "M4") (pinfunction "CSI0_DAT14_M4") (pintype "bidirectional"))
    )
    (net (code "61") (name "CSI0_DAT15") (class "Default")
      (node (ref "U1") (pin "M5") (pinfunction "CSI0_DAT15_M5") (pintype "bidirectional"))
    )
    (net (code "62") (name "CSI0_DAT16") (class "Default")
      (node (ref "U1") (pin "L4") (pinfunction "CSI0_DAT16_L4") (pintype "bidirectional"))
    )
    (net (code "63") (name "CSI0_DAT17") (class "Default")
      (node (ref "U1") (pin "L3") (pinfunction "CSI0_DAT17_L3") (pintype "bidirectional"))
    )
    (net (code "64") (name "CSI0_DAT18") (class "Default")
      (node (ref "U1") (pin "M6") (pinfunction "CSI0_DAT18_M6") (pintype "bidirectional"))
    )
    (net (code "65") (name "CSI0_DAT19") (class "Default")
      (node (ref "U1") (pin "L6") (pinfunction "CSI0_DAT19_L6") (pintype "bidirectional"))
    )
    (net (code "66") (name "CSI0_HSYNCH") (class "Default")
      (node (ref "U1") (pin "P4") (pinfunction "CSI0_MCLK_P4") (pintype "bidirectional"))
    )
    (net (code "67") (name "CSI0_PIXCLK") (class "Default")
      (node (ref "U1") (pin "P1") (pinfunction "CSI0_PIXCLK_P1") (pintype "bidirectional"))
    )
    (net (code "68") (name "CSI0_PWN") (class "Default")
      (node (ref "U1") (pin "A21") (pinfunction "SD1_DAT0_A21") (pintype "bidirectional"))
    )
    (net (code "69") (name "CSI0_RST_B") (class "Default")
      (node (ref "U1") (pin "C20") (pinfunction "SD1_DAT1_C20") (pintype "bidirectional"))
    )
    (net (code "70") (name "CSI0_VSYNCH") (class "Default")
      (node (ref "U1") (pin "N2") (pinfunction "CSI0_VSYNC_N2") (pintype "bidirectional"))
    )
    (net (code "71") (name "CSI_CLK0M") (class "Default")
      (node (ref "U1") (pin "F4") (pinfunction "CSI_CLK0M_F4") (pintype "input"))
    )
    (net (code "72") (name "CSI_CLK0P") (class "Default")
      (node (ref "U1") (pin "F3") (pinfunction "CSI_CLK0P_F3") (pintype "input"))
    )
    (net (code "73") (name "CSI_D0M") (class "Default")
      (node (ref "U1") (pin "E4") (pinfunction "CSI_D0M_E4") (pintype "input"))
    )
    (net (code "74") (name "CSI_D0P") (class "Default")
      (node (ref "U1") (pin "E3") (pinfunction "CSI_D0P_E3") (pintype "input"))
    )
    (net (code "75") (name "CSI_D1M") (class "Default")
      (node (ref "U1") (pin "D1") (pinfunction "CSI_D1M_D1") (pintype "input"))
    )
    (net (code "76") (name "CSI_D1P") (class "Default")
      (node (ref "U1") (pin "D2") (pinfunction "CSI_D1P_D2") (pintype "input"))
    )
    (net (code "77") (name "CSI_PWN") (class "Default")
      (node (ref "U1") (pin "E19") (pinfunction "SD1_DAT2_E19") (pintype "bidirectional"))
    )
    (net (code "78") (name "CSI_RST_B") (class "Default")
      (node (ref "U1") (pin "D20") (pinfunction "SD1_CLK_D20") (pintype "bidirectional"))
    )
    (net (code "79") (name "CSPI1_CLK") (class "Default")
      (node (ref "U1") (pin "W5") (pinfunction "KEY_COL0_W5") (pintype "bidirectional"))
    )
    (net (code "80") (name "CSPI1_CS0") (class "Default")
      (node (ref "U1") (pin "U6") (pinfunction "KEY_ROW1_U6") (pintype "bidirectional"))
    )
    (net (code "81") (name "CSPI1_MISO") (class "Default")
      (node (ref "U1") (pin "U7") (pinfunction "KEY_COL1_U7") (pintype "bidirectional"))
    )
    (net (code "82") (name "CSPI1_MOSI") (class "Default")
      (node (ref "U1") (pin "V6") (pinfunction "KEY_ROW0_V6") (pintype "bidirectional"))
    )
    (net (code "83") (name "DI0_D0_CS") (class "Default")
      (node (ref "R132") (pin "1") (pinfunction "1_1") (pintype "passive"))
    )
    (net (code "84") (name "DI0_D1_CS") (class "Default")
      (node (ref "R122") (pin "1") (pinfunction "1_1") (pintype "passive"))
    )
    (net (code "85") (name "DISP0_CLK") (class "Default")
      (node (ref "U1") (pin "N19") (pinfunction "DI0_DISP_CLK_N19") (pintype "bidirectional"))
    )
    (net (code "86") (name "DISP0_CNTRST") (class "Default")
      (node (ref "U1") (pin "P25") (pinfunction "DI0_PIN4_P25") (pintype "bidirectional"))
    )
    (net (code "87") (name "DISP0_CONTRAST") (class "Default")
      (node (ref "U514") (pin "4") (pinfunction "B_4") (pintype "output"))
    )
    (net (code "88") (name "DISP0_DAT0") (class "Default")
      (node (ref "U1") (pin "P24") (pinfunction "DISP0_DAT0_P24") (pintype "bidirectional"))
    )
    (net (code "89") (name "DISP0_DAT1") (class "Default")
      (node (ref "U1") (pin "P22") (pinfunction "DISP0_DAT1_P22") (pintype "bidirectional"))
    )
    (net (code "90") (name "DISP0_DAT2") (class "Default")
      (node (ref "U1") (pin "P23") (pinfunction "DISP0_DAT2_P23") (pintype "bidirectional"))
    )
    (net (code "91") (name "DISP0_DAT3") (class "Default")
      (node (ref "U1") (pin "P21") (pinfunction "DISP0_DAT3_P21") (pintype "bidirectional"))
    )
    (net (code "92") (name "DISP0_DAT4") (class "Default")
      (node (ref "U1") (pin "P20") (pinfunction "DISP0_DAT4_P20") (pintype "bidirectional"))
    )
    (net (code "93") (name "DISP0_DAT5") (class "Default")
      (node (ref "U1") (pin "R25") (pinfunction "DISP0_DAT5_R25") (pintype "bidirectional"))
    )
    (net (code "94") (name "DISP0_DAT6") (class "Default")
      (node (ref "U1") (pin "R23") (pinfunction "DISP0_DAT6_R23") (pintype "bidirectional"))
    )
    (net (code "95") (name "DISP0_DAT7") (class "Default")
      (node (ref "U1") (pin "R24") (pinfunction "DISP0_DAT7_R24") (pintype "bidirectional"))
    )
    (net (code "96") (name "DISP0_DAT8") (class "Default")
      (node (ref "U1") (pin "R22") (pinfunction "DISP0_DAT8_R22") (pintype "bidirectional"))
    )
    (net (code "97") (name "DISP0_DAT9") (class "Default")
      (node (ref "U1") (pin "T25") (pinfunction "DISP0_DAT9_T25") (pintype "bidirectional"))
    )
    (net (code "98") (name "DISP0_DAT10") (class "Default")
      (node (ref "U1") (pin "R21") (pinfunction "DISP0_DAT10_R21") (pintype "bidirectional"))
    )
    (net (code "99") (name "DISP0_DAT11") (class "Default")
      (node (ref "U1") (pin "T23") (pinfunction "DISP0_DAT11_T23") (pintype "bidirectional"))
    )
    (net (code "100") (name "DISP0_DAT12") (class "Default")
      (node (ref "U1") (pin "T24") (pinfunction "DISP0_DAT12_T24") (pintype "bidirectional"))
    )
    (net (code "101") (name "DISP0_DAT13") (class "Default")
      (node (ref "U1") (pin "R20") (pinfunction "DISP0_DAT13_R20") (pintype "bidirectional"))
    )
    (net (code "102") (name "DISP0_DAT14") (class "Default")
      (node (ref "U1") (pin "U25") (pinfunction "DISP0_DAT14_U25") (pintype "bidirectional"))
    )
    (net (code "103") (name "DISP0_DAT15") (class "Default")
      (node (ref "U1") (pin "T22") (pinfunction "DISP0_DAT15_T22") (pintype "bidirectional"))
    )
    (net (code "104") (name "DISP0_DAT16") (class "Default")
      (node (ref "U1") (pin "T21") (pinfunction "DISP0_DAT16_T21") (pintype "bidirectional"))
    )
    (net (code "105") (name "DISP0_DAT17") (class "Default")
      (node (ref "U1") (pin "U24") (pinfunction "DISP0_DAT17_U24") (pintype "bidirectional"))
    )
    (net (code "106") (name "DISP0_DAT18") (class "Default")
      (node (ref "U1") (pin "V25") (pinfunction "DISP0_DAT18_V25") (pintype "bidirectional"))
    )
    (net (code "107") (name "DISP0_DAT19") (class "Default")
      (node (ref "U1") (pin "U23") (pinfunction "DISP0_DAT19_U23") (pintype "bidirectional"))
    )
    (net (code "108") (name "DISP0_DAT20") (class "Default")
      (node (ref "U1") (pin "U22") (pinfunction "DISP0_DAT20_U22") (pintype "bidirectional"))
    )
    (net (code "109") (name "DISP0_DAT21") (class "Default")
      (node (ref "U1") (pin "T20") (pinfunction "DISP0_DAT21_T20") (pintype "bidirectional"))
    )
    (net (code "110") (name "DISP0_DAT22") (class "Default")
      (node (ref "U1") (pin "V24") (pinfunction "DISP0_DAT22_V24") (pintype "bidirectional"))
    )
    (net (code "111") (name "DISP0_DAT23") (class "Default")
      (node (ref "U1") (pin "W24") (pinfunction "DISP0_DAT23_W24") (pintype "bidirectional"))
    )
    (net (code "112") (name "DISP0_DRDY") (class "Default")
      (node (ref "U1") (pin "N21") (pinfunction "DI0_PIN15_N21") (pintype "bidirectional"))
    )
    (net (code "113") (name "DISP0_HSYNCH") (class "Default")
      (node (ref "U1") (pin "N25") (pinfunction "DI0_PIN2_N25") (pintype "bidirectional"))
    )
    (net (code "114") (name "DISP0_PWR_EN") (class "Default")
      (node (ref "U1") (pin "U20") (pinfunction "ENET_TXD0_U20") (pintype "bidirectional"))
    )
    (net (code "115") (name "DISP0_RD") (class "Default")
      (node (ref "R135") (pin "1") (pinfunction "1_1") (pintype "passive"))
    )
    (net (code "116") (name "DISP0_RST_B") (class "Default")
      (node (ref "R120") (pin "1") (pinfunction "1_1") (pintype "passive"))
    )
    (net (code "117") (name "DISP0_SER_RS") (class "Default")
      (node (ref "R69") (pin "1") (pinfunction "1_1") (pintype "passive"))
      (node (ref "U1") (pin "R5") (pinfunction "GPIO_8_R5") (pintype "bidirectional"))
    )
    (net (code "118") (name "DISP0_VSYNCH") (class "Default")
      (node (ref "U1") (pin "N20") (pinfunction "DI0_PIN3_N20") (pintype "bidirectional"))
    )
    (net (code "119") (name "DISP0_WR") (class "Default")
      (node (ref "U1") (pin "E15") (pinfunction "~{NANDF_WP}_E15") (pintype "bidirectional"))
    )
    (net (code "120") (name "DISP_PWR_EN") (class "Default")
      (node (ref "U1") (pin "C16") (pinfunction "NANDF_CS1_C16") (pintype "bidirectional"))
    )
    (net (code "121") (name "DISP_RST_B") (class "Default")
      (node (ref "U1") (pin "F15") (pinfunction "NANDF_CS0_F15") (pintype "bidirectional"))
    )
    (net (code "122") (name "DOK_B") (class "Default")
      (node (ref "R627") (pin "1") (pinfunction "1_1") (pintype "passive"))
    )
    (net (code "123") (name "DSI_CLK0M") (class "Default")
      (node (ref "U1") (pin "H3") (pinfunction "DSI_CLK0M_H3") (pintype "output"))
    )
    (net (code "124") (name "DSI_CLK0P") (class "Default")
      (node (ref "U1") (pin "H4") (pinfunction "DSI_CLK0P_H4") (pintype "output"))
    )
    (net (code "125") (name "DSI_D0M") (class "Default")
      (node (ref "U1") (pin "G2") (pinfunction "DSI_D0M_G2") (pintype "output"))
    )
    (net (code "126") (name "DSI_D0P") (class "Default")
      (node (ref "U1") (pin "G1") (pinfunction "DSI_D0P_G1") (pintype "output"))
    )
    (net (code "127") (name "DSI_D1M") (class "Default")
      (node (ref "U1") (pin "H2") (pinfunction "DSI_D1M_H2") (pintype "output"))
    )
    (net (code "128") (name "DSI_D1P") (class "Default")
      (node (ref "U1") (pin "H1") (pinfunction "DSI_D1P_H1") (pintype "output"))
    )
    (net (code "129") (name "EIM_A16") (class "Default")
      (node (ref "U1") (pin "H25") (pinfunction "EIM_A16_H25") (pintype "bidirectional"))
    )
    (net (code "130") (name "EIM_A17") (class "Default")
      (node (ref "U1") (pin "G24") (pinfunction "EIM_A17_G24") (pintype "bidirectional"))
    )
    (net (code "131") (name "EIM_A18") (class "Default")
      (node (ref "U1") (pin "J22") (pinfunction "EIM_A18_J22") (pintype "bidirectional"))
    )
    (net (code "132") (name "EIM_A19") (class "Default")
      (node (ref "U1") (pin "G25") (pinfunction "EIM_A19_G25") (pintype "bidirectional"))
    )
    (net (code "133") (name "EIM_A20") (class "Default")
      (node (ref "U1") (pin "H22") (pinfunction "EIM_A20_H22") (pintype "bidirectional"))
    )
    (net (code "134") (name "EIM_A21") (class "Default")
      (node (ref "U1") (pin "H23") (pinfunction "EIM_A21_H23") (pintype "bidirectional"))
    )
    (net (code "135") (name "EIM_A22") (class "Default")
      (node (ref "U1") (pin "F24") (pinfunction "EIM_A22_F24") (pintype "bidirectional"))
    )
    (net (code "136") (name "EIM_A23") (class "Default")
      (node (ref "U1") (pin "J21") (pinfunction "EIM_A23_J21") (pintype "bidirectional"))
    )
    (net (code "137") (name "EIM_A24") (class "Default")
      (node (ref "U1") (pin "F25") (pinfunction "EIM_A24_F25") (pintype "bidirectional"))
    )
    (net (code "138") (name "EIM_A25") (class "Default")
      (node (ref "R138") (pin "2") (pinfunction "2_2") (pintype "passive"))
      (node (ref "U1") (pin "H19") (pinfunction "EIM_A25_H19") (pintype "bidirectional"))
    )
    (net (code "139") (name "EIM_BCLK") (class "Default")
      (node (ref "R122") (pin "2") (pinfunction "2_2") (pintype "passive"))
      (node (ref "U1") (pin "N22") (pinfunction "EIM_BCLK_N22") (pintype "bidirectional"))
    )
    (net (code "140") (name "EIM_CS0") (class "Default")
      (node (ref "U1") (pin "H24") (pinfunction "EIM_CS0_H24") (pintype "bidirectional"))
    )
    (net (code "141") (name "EIM_CS1") (class "Default")
      (node (ref "R627") (pin "2") (pinfunction "2_2") (pintype "passive"))
      (node (ref "U1") (pin "J23") (pinfunction "EIM_CS1_J23") (pintype "bidirectional"))
    )
    (net (code "142") (name "EIM_D16") (class "Default")
      (node (ref "R168") (pin "2") (pinfunction "2_2") (pintype "passive"))
      (node (ref "R218") (pin "2") (pinfunction "2_2") (pintype "passive"))
      (node (ref "U1") (pin "C25") (pinfunction "EIM_D16_C25") (pintype "bidirectional"))
    )
    (net (code "143") (name "EIM_D17") (class "Default")
      (node (ref "U1") (pin "F21") (pinfunction "EIM_D17_F21") (pintype "bidirectional"))
    )
    (net (code "144") (name "EIM_D18") (class "Default")
      (node (ref "R129") (pin "2") (pinfunction "2_2") (pintype "passive"))
      (node (ref "U1") (pin "D24") (pinfunction "EIM_D18_D24") (pintype "bidirectional"))
    )
    (net (code "145") (name "EIM_D19") (class "Default")
      (node (ref "R123") (pin "2") (pinfunction "2_2") (pintype "passive"))
      (node (ref "U1") (pin "G21") (pinfunction "EIM_D19_G21") (pintype "bidirectional"))
    )
    (net (code "146") (name "EIM_D20") (class "Default")
      (node (ref "U1") (pin "G20") (pinfunction "EIM_D20_G20") (pintype "bidirectional"))
    )
    (net (code "147") (name "EIM_D23") (class "Default")
      (node (ref "R139") (pin "2") (pinfunction "2_2") (pintype "passive"))
      (node (ref "U1") (pin "D25") (pinfunction "EIM_D23_D25") (pintype "bidirectional"))
    )
    (net (code "148") (name "EIM_D26") (class "Default")
      (node (ref "R128") (pin "2") (pinfunction "2_2") (pintype "passive"))
      (node (ref "U1") (pin "E24") (pinfunction "EIM_D26_E24") (pintype "bidirectional"))
    )
    (net (code "149") (name "EIM_D27") (class "Default")
      (node (ref "U1") (pin "E25") (pinfunction "EIM_D27_E25") (pintype "bidirectional"))
    )
    (net (code "150") (name "EIM_D28") (class "Default")
      (node (ref "R135") (pin "2") (pinfunction "2_2") (pintype "passive"))
      (node (ref "U1") (pin "G23") (pinfunction "EIM_D28_G23") (pintype "bidirectional"))
    )
    (net (code "151") (name "EIM_D30") (class "Default")
      (node (ref "R134") (pin "2") (pinfunction "2_2") (pintype "passive"))
      (node (ref "U1") (pin "J20") (pinfunction "EIM_D30_J20") (pintype "bidirectional"))
    )
    (net (code "152") (name "EIM_D31") (class "Default")
      (node (ref "U1") (pin "H21") (pinfunction "EIM_D31_H21") (pintype "bidirectional"))
    )
    (net (code "153") (name "EIM_DA0") (class "Default")
      (node (ref "R131") (pin "2") (pinfunction "2_2") (pintype "passive"))
      (node (ref "U1") (pin "L20") (pinfunction "EIM_DA0_L20") (pintype "bidirectional"))
    )
    (net (code "154") (name "EIM_DA1") (class "Default")
      (node (ref "U1") (pin "J25") (pinfunction "EIM_DA1_J25") (pintype "bidirectional"))
    )
    (net (code "155") (name "EIM_DA2") (class "Default")
      (node (ref "U1") (pin "L21") (pinfunction "EIM_DA2_L21") (pintype "bidirectional"))
    )
    (net (code "156") (name "EIM_DA3") (class "Default")
      (node (ref "U1") (pin "K24") (pinfunction "EIM_DA3_K24") (pintype "bidirectional"))
    )
    (net (code "157") (name "EIM_DA4") (class "Default")
      (node (ref "U1") (pin "L22") (pinfunction "EIM_DA4_L22") (pintype "bidirectional"))
    )
    (net (code "158") (name "EIM_DA5") (class "Default")
      (node (ref "U1") (pin "L23") (pinfunction "EIM_DA5_L23") (pintype "bidirectional"))
    )
    (net (code "159") (name "EIM_DA6") (class "Default")
      (node (ref "U1") (pin "K25") (pinfunction "EIM_DA6_K25") (pintype "bidirectional"))
    )
    (net (code "160") (name "EIM_DA7") (class "Default")
      (node (ref "U1") (pin "L25") (pinfunction "EIM_DA7_L25") (pintype "bidirectional"))
    )
    (net (code "161") (name "EIM_DA8") (class "Default")
      (node (ref "R120") (pin "2") (pinfunction "2_2") (pintype "passive"))
      (node (ref "U1") (pin "L24") (pinfunction "EIM_DA8_L24") (pintype "bidirectional"))
    )
    (net (code "162") (name "EIM_DA9") (class "Default")
      (node (ref "R171") (pin "2") (pinfunction "2_2") (pintype "passive"))
      (node (ref "U1") (pin "M21") (pinfunction "EIM_DA9_M21") (pintype "bidirectional"))
    )
    (net (code "163") (name "EIM_DA10") (class "Default")
      (node (ref "U1") (pin "M22") (pinfunction "EIM_DA10_M22") (pintype "bidirectional"))
    )
    (net (code "164") (name "EIM_DA11") (class "Default")
      (node (ref "U1") (pin "M20") (pinfunction "EIM_DA11_M20") (pintype "bidirectional"))
    )
    (net (code "165") (name "EIM_DA12") (class "Default")
      (node (ref "U1") (pin "M24") (pinfunction "EIM_DA12_M24") (pintype "bidirectional"))
    )
    (net (code "166") (name "EIM_DA13") (class "Default")
      (node (ref "R133") (pin "2") (pinfunction "2_2") (pintype "passive"))
      (node (ref "U1") (pin "M23") (pinfunction "EIM_DA13_M23") (pintype "bidirectional"))
    )
    (net (code "167") (name "EIM_DA14") (class "Default")
      (node (ref "R121") (pin "2") (pinfunction "2_2") (pintype "passive"))
      (node (ref "U1") (pin "N23") (pinfunction "EIM_DA14_N23") (pintype "bidirectional"))
    )
    (net (code "168") (name "EIM_DA15") (class "Default")
      (node (ref "R167") (pin "2") (pinfunction "2_2") (pintype "passive"))
      (node (ref "R217") (pin "2") (pinfunction "2_2") (pintype "passive"))
      (node (ref "U1") (pin "N24") (pinfunction "EIM_DA15_N24") (pintype "bidirectional"))
    )
    (net (code "169") (name "EIM_EB0") (class "Default")
      (node (ref "R124") (pin "2") (pinfunction "2_2") (pintype "passive"))
      (node (ref "U1") (pin "K21") (pinfunction "EIM_EB0_K21") (pintype "bidirectional"))
    )
    (net (code "170") (name "EIM_EB1") (class "Default")
      (node (ref "U1") (pin "K23") (pinfunction "EIM_EB1_K23") (pintype "bidirectional"))
    )
    (net (code "171") (name "EIM_EB2") (class "Default")
      (node (ref "R219") (pin "2") (pinfunction "2_2") (pintype "passive"))
      (node (ref "U1") (pin "E22") (pinfunction "EIM_EB2_E22") (pintype "bidirectional"))
    )
    (net (code "172") (name "EIM_EB3") (class "Default")
      (node (ref "R136") (pin "2") (pinfunction "2_2") (pintype "passive"))
      (node (ref "U1") (pin "F23") (pinfunction "EIM_EB3_F23") (pintype "bidirectional"))
    )
    (net (code "173") (name "EIM_LBA") (class "Default")
      (node (ref "U1") (pin "K22") (pinfunction "EIM_LBA_K22") (pintype "bidirectional"))
    )
    (net (code "174") (name "EIM_OE") (class "Default")
      (node (ref "U1") (pin "J24") (pinfunction "EIM_OE_J24") (pintype "bidirectional"))
    )
    (net (code "175") (name "EIM_RW") (class "Default")
      (node (ref "U1") (pin "K20") (pinfunction "EIM_RW_K20") (pintype "bidirectional"))
    )
    (net (code "176") (name "EIM_WAIT") (class "Default")
      (node (ref "R132") (pin "2") (pinfunction "2_2") (pintype "passive"))
      (node (ref "U1") (pin "M25") (pinfunction "EIM_WAIT_M25") (pintype "bidirectional"))
    )
    (net (code "177") (name "ENET_REF_CLK") (class "Default")
      (node (ref "C726") (pin "1") (pinfunction "1_1") (pintype "passive"))
    )
    (net (code "178") (name "ETH_3V3") (class "Default")
      (node (ref "R623") (pin "1") (pinfunction "1_1") (pintype "passive"))
    )
    (net (code "179") (name "ETH_WOL_INT") (class "Default")
      (node (ref "U1") (pin "V21") (pinfunction "ENET_TX_EN_V21") (pintype "bidirectional"))
    )
    (net (code "180") (name "GEN_1V8") (class "Default")
      (node (ref "C641") (pin "1") (pinfunction "1_1") (pintype "passive"))
      (node (ref "U514") (pin "1") (pinfunction "VCCA_1") (pintype "power_in"))
    )
    (net (code "181") (name "GEN_2V5") (class "Default")
      (node (ref "R46") (pin "1") (pinfunction "1_1") (pintype "passive"))
      (node (ref "R50") (pin "1") (pinfunction "1_1") (pintype "passive"))
      (node (ref "R600") (pin "1") (pinfunction "1_1") (pintype "passive"))
      (node (ref "R87") (pin "1") (pinfunction "1_1") (pintype "passive"))
    )
    (net (code "182") (name "GEN_3V3") (class "Default")
      (node (ref "C622") (pin "1") (pinfunction "1_1") (pintype "passive"))
      (node (ref "U514") (pin "6") (pinfunction "VCCB_6") (pintype "power_in"))
    )
    (net (code "183") (name "GND") (class "Default")
      (node (ref "C39") (pin "2") (pinfunction "2_2") (pintype "passive"))
      (node (ref "C51") (pin "2") (pinfunction "2_2") (pintype "passive"))
      (node (ref "C55") (pin "2") (pinfunction "2_2") (pintype "passive"))
      (node (ref "C606") (pin "2") (pinfunction "2_2") (pintype "passive"))
      (node (ref "C607") (pin "2") (pinfunction "2_2") (pintype "passive"))
      (node (ref "C608") (pin "2") (pinfunction "2_2") (pintype "passive"))
      (node (ref "C609") (pin "2") (pinfunction "2_2") (pintype "passive"))
      (node (ref "C610") (pin "2") (pinfunction "2_2") (pintype "passive"))
      (node (ref "C622") (pin "2") (pinfunction "2_2") (pintype "passive"))
      (node (ref "C624") (pin "2") (pinfunction "2_2") (pintype "passive"))
      (node (ref "C625") (pin "2") (pinfunction "2_2") (pintype "passive"))
      (node (ref "C626") (pin "2") (pinfunction "2_2") (pintype "passive"))
      (node (ref "C627") (pin "2") (pinfunction "2_2") (pintype "passive"))
      (node (ref "C632") (pin "2") (pinfunction "2_2") (pintype "passive"))
      (node (ref "C633") (pin "2") (pinfunction "2_2") (pintype "passive"))
      (node (ref "C635") (pin "2") (pinfunction "2_2") (pintype "passive"))
      (node (ref "C638") (pin "2") (pinfunction "2_2") (pintype "passive"))
      (node (ref "C639") (pin "2") (pinfunction "2_2") (pintype "passive"))
      (node (ref "C640") (pin "2") (pinfunction "2_2") (pintype "passive"))
      (node (ref "C641") (pin "2") (pinfunction "2_2") (pintype "passive"))
      (node (ref "C642") (pin "2") (pinfunction "2_2") (pintype "passive"))
      (node (ref "C651") (pin "2") (pinfunction "2_2") (pintype "passive"))
      (node (ref "C668") (pin "2") (pinfunction "2_2") (pintype "passive"))
      (node (ref "C673") (pin "2") (pinfunction "2_2") (pintype "passive"))
      (node (ref "C678") (pin "2") (pinfunction "2_2") (pintype "passive"))
      (node (ref "C681") (pin "2") (pinfunction "2_2") (pintype "passive"))
      (node (ref "R216") (pin "2") (pinfunction "2_2") (pintype "passive"))
      (node (ref "R37") (pin "2") (pinfunction "2_2") (pintype "passive"))
      (node (ref "R38") (pin "2") (pinfunction "2_2") (pintype "passive"))
      (node (ref "R604") (pin "2") (pinfunction "2_2") (pintype "passive"))
      (node (ref "R605") (pin "2") (pinfunction "2_2") (pintype "passive"))
      (node (ref "R619") (pin "2") (pinfunction "2_2") (pintype "passive"))
      (node (ref "R624") (pin "2") (pinfunction "2_2") (pintype "passive"))
      (node (ref "R656") (pin "2") (pinfunction "2_2") (pintype "passive"))
      (node (ref "U514") (pin "3") (pinfunction "GND_3") (pintype "power_in"))
      (node (ref "Y1") (pin "2") (pinfunction "2_2") (pintype "passive"))
      (node (ref "Y1") (pin "4") (pinfunction "4_4") (pintype "passive"))
    )
    (net (code "184") (name "GPIO_0_CLKO") (class "Default")
      (node (ref "U1") (pin "T5") (pinfunction "GPIO_0_T5") (pintype "bidirectional"))
    )
    (net (code "185") (name "GPS_PPS") (class "Default")
      (node (ref "R129") (pin "1") (pinfunction "1_1") (pintype "passive"))
    )
    (net (code "186") (name "GPS_PWREN") (class "Default")
      (node (ref "R131") (pin "1") (pinfunction "1_1") (pintype "passive"))
    )
    (net (code "187") (name "GPS_RESET_B") (class "Default")
      (node (ref "R124") (pin "1") (pinfunction "1_1") (pintype "passive"))
    )
    (net (code "188") (name "HDMI_CEC_IN") (class "Default")
      (node (ref "R652") (pin "2") (pinfunction "2_2") (pintype "passive"))
      (node (ref "R653") (pin "2") (pinfunction "2_2") (pintype "passive"))
    )
    (net (code "189") (name "HDMI_CLKM") (class "Default")
      (node (ref "U1") (pin "J5") (pinfunction "HDMI_CLKM_J5") (pintype "output"))
    )
    (net (code "190") (name "HDMI_CLKP") (class "Default")
      (node (ref "U1") (pin "J6") (pinfunction "HDMI_CLKP_J6") (pintype "output"))
    )
    (net (code "191") (name "HDMI_D0M") (class "Default")
      (node (ref "U1") (pin "K5") (pinfunction "HDMI_D0M_K5") (pintype "output"))
    )
    (net (code "192") (name "HDMI_D0P") (class "Default")
      (node (ref "U1") (pin "K6") (pinfunction "HDMI_D0P_K6") (pintype "output"))
    )
    (net (code "193") (name "HDMI_D1M") (class "Default")
      (node (ref "U1") (pin "J3") (pinfunction "HDMI_D1M_J3") (pintype "output"))
    )
    (net (code "194") (name "HDMI_D1P") (class "Default")
      (node (ref "U1") (pin "J4") (pinfunction "HDMI_D1P_J4") (pintype "output"))
    )
    (net (code "195") (name "HDMI_D2M") (class "Default")
      (node (ref "U1") (pin "K3") (pinfunction "HDMI_D2M_K3") (pintype "output"))
    )
    (net (code "196") (name "HDMI_D2P") (class "Default")
      (node (ref "U1") (pin "K4") (pinfunction "HDMI_D2P_K4") (pintype "output"))
    )
    (net (code "197") (name "HDMI_DDC_CLK_IN") (class "Default")
      (node (ref "R219") (pin "1") (pinfunction "1_1") (pintype "passive"))
    )
    (net (code "198") (name "HDMI_DDC_DAT_IN") (class "Default")
      (node (ref "R218") (pin "1") (pinfunction "1_1") (pintype "passive"))
    )
    (net (code "199") (name "HDMI_HPD") (class "Default")
      (node (ref "U1") (pin "K1") (pinfunction "HDMI_HPD_K1") (pintype "input"))
    )
    (net (code "200") (name "HEADPHONE_DET") (class "Default")
      (node (ref "R553") (pin "1") (pinfunction "1_1") (pintype "passive"))
    )
    (net (code "201") (name "I2C1_SCL") (class "Default")
      (node (ref "U1") (pin "N5") (pinfunction "CSI0_DAT9_N5") (pintype "bidirectional"))
    )
    (net (code "202") (name "I2C1_SDA") (class "Default")
      (node (ref "U1") (pin "N6") (pinfunction "CSI0_DAT8_N6") (pintype "bidirectional"))
    )
    (net (code "203") (name "I2C2_SCL") (class "Default")
      (node (ref "U1") (pin "U5") (pinfunction "KEY_COL3_U5") (pintype "bidirectional"))
    )
    (net (code "204") (name "I2C2_SDA") (class "Default")
      (node (ref "U1") (pin "T7") (pinfunction "KEY_ROW3_T7") (pintype "bidirectional"))
    )
    (net (code "205") (name "I2C3_SCL") (class "Default")
      (node (ref "U1") (pin "R7") (pinfunction "GPIO_3_R7") (pintype "bidirectional"))
    )
    (net (code "206") (name "I2C3_SDA") (class "Default")
      (node (ref "U1") (pin "T3") (pinfunction "GPIO_6_T3") (pintype "bidirectional"))
    )
    (net (code "207") (name "JTAG_MOD") (class "Default")
      (node (ref "U1") (pin "H6") (pinfunction "JTAG_MOD_H6") (pintype "input"))
    )
    (net (code "208") (name "JTAG_TCK") (class "Default")
      (node (ref "U1") (pin "H5") (pinfunction "JTAG_TCK_H5") (pintype "input"))
    )
    (net (code "209") (name "JTAG_TDI") (class "Default")
      (node (ref "U1") (pin "G5") (pinfunction "JTAG_TDI_G5") (pintype "input"))
    )
    (net (code "210") (name "JTAG_TDO") (class "Default")
      (node (ref "U1") (pin "G6") (pinfunction "JTAG_TDO_G6") (pintype "output"))
    )
    (net (code "211") (name "JTAG_TMS") (class "Default")
      (node (ref "U1") (pin "C3") (pinfunction "JTAG_TMS_C3") (pintype "input"))
    )
    (net (code "212") (name "JTAG_nTRST") (class "Default")
      (node (ref "U1") (pin "C2") (pinfunction "~{JTAG_TRST}_C2") (pintype "input"))
    )
    (net (code "213") (name "KEY_COL4") (class "Default")
      (node (ref "R36") (pin "1") (pinfunction "1_1") (pintype "passive"))
      (node (ref "U1") (pin "T6") (pinfunction "KEY_COL4_T6") (pintype "bidirectional"))
    )
    (net (code "214") (name "KEY_COL5") (class "Default")
      (node (ref "R661") (pin "1") (pinfunction "1_1") (pintype "passive"))
      (node (ref "U1") (pin "P5") (pinfunction "GPIO_19_P5") (pintype "bidirectional"))
    )
    (net (code "215") (name "KEY_COL6") (class "Default")
      (node (ref "R597") (pin "1") (pinfunction "1_1") (pintype "passive"))
      (node (ref "U1") (pin "T2") (pinfunction "GPIO_9_T2") (pintype "bidirectional"))
    )
    (net (code "216") (name "KEY_COL7") (class "Default")
      (node (ref "R594") (pin "1") (pinfunction "1_1") (pintype "passive"))
      (node (ref "U1") (pin "R6") (pinfunction "GPIO_4_R6") (pintype "bidirectional"))
    )
    (net (code "217") (name "KEY_ROW4") (class "Default")
      (node (ref "R676") (pin "1") (pinfunction "1_1") (pintype "passive"))
      (node (ref "U1") (pin "V5") (pinfunction "KEY_ROW4_V5") (pintype "bidirectional"))
    )
    (net (code "218") (name "KEY_ROW5") (class "Default")
      (node (ref "R300") (pin "1") (pinfunction "1_1") (pintype "passive"))
      (node (ref "U1") (pin "T4") (pinfunction "GPIO_1_T4") (pintype "bidirectional"))
    )
    (net (code "219") (name "KEY_ROW6") (class "Default")
      (node (ref "R588") (pin "1") (pinfunction "1_1") (pintype "passive"))
      (node (ref "U1") (pin "T1") (pinfunction "GPIO_2_T1") (pintype "bidirectional"))
    )
    (net (code "220") (name "KEY_ROW7") (class "Default")
      (node (ref "R66") (pin "1") (pinfunction "1_1") (pintype "passive"))
      (node (ref "U1") (pin "R4") (pinfunction "GPIO_5_R4") (pintype "bidirectional"))
    )
    (net (code "221") (name "KEY_VOL_DN") (class "Default")
      (node (ref "R66") (pin "2") (pinfunction "2_2") (pintype "passive"))
    )
    (net (code "222") (name "KEY_VOL_UP") (class "Default")
      (node (ref "R594") (pin "2") (pinfunction "2_2") (pintype "passive"))
    )
    (net (code "223") (name "LVDS0_CLK_N") (class "Default")
      (node (ref "U1") (pin "V4") (pinfunction "LVDS0_CLK_N_V4") (pintype "output"))
    )
    (net (code "224") (name "LVDS0_CLK_P") (class "Default")
      (node (ref "U1") (pin "V3") (pinfunction "LVDS0_CLK_P_V3") (pintype "output"))
    )
    (net (code "225") (name "LVDS0_TX0_N") (class "Default")
      (node (ref "U1") (pin "U2") (pinfunction "LVDS0_TX0_N_U2") (pintype "output"))
    )
    (net (code "226") (name "LVDS0_TX0_P") (class "Default")
      (node (ref "U1") (pin "U1") (pinfunction "LVDS0_TX0_P_U1") (pintype "output"))
    )
    (net (code "227") (name "LVDS0_TX1_N") (class "Default")
      (node (ref "U1") (pin "U4") (pinfunction "LVDS0_TX1_N_U4") (pintype "output"))
    )
    (net (code "228") (name "LVDS0_TX1_P") (class "Default")
      (node (ref "U1") (pin "U3") (pinfunction "LVDS0_TX1_P_U3") (pintype "output"))
    )
    (net (code "229") (name "LVDS0_TX2_N") (class "Default")
      (node (ref "U1") (pin "V2") (pinfunction "LVDS0_TX2_N_V2") (pintype "output"))
    )
    (net (code "230") (name "LVDS0_TX2_P") (class "Default")
      (node (ref "U1") (pin "V1") (pinfunction "LVDS0_TX2_P_V1") (pintype "output"))
    )
    (net (code "231") (name "LVDS1_CLK_N") (class "Default")
      (node (ref "U1") (pin "Y3") (pinfunction "LVDS1_CLK_N_Y3") (pintype "output"))
    )
    (net (code "232") (name "LVDS1_CLK_P") (class "Default")
      (node (ref "U1") (pin "Y4") (pinfunction "LVDS1_CLK_P_Y4") (pintype "output"))
    )
    (net (code "233") (name "LVDS1_TX0_N") (class "Default")
      (node (ref "U1") (pin "Y1") (pinfunction "LVDS1_TX0_N_Y1") (pintype "output"))
    )
    (net (code "234") (name "LVDS1_TX0_P") (class "Default")
      (node (ref "U1") (pin "Y2") (pinfunction "LVDS1_TX0_P_Y2") (pintype "output"))
    )
    (net (code "235") (name "LVDS1_TX1_N") (class "Default")
      (node (ref "U1") (pin "AA2") (pinfunction "LVDS1_TX1_N_AA2") (pintype "output"))
    )
    (net (code "236") (name "LVDS1_TX1_P") (class "Default")
      (node (ref "U1") (pin "AA1") (pinfunction "LVDS1_TX1_P_AA1") (pintype "output"))
    )
    (net (code "237") (name "LVDS1_TX2_N") (class "Default")
      (node (ref "U1") (pin "AB1") (pinfunction "LVDS1_TX2_N_AB1") (pintype "output"))
    )
    (net (code "238") (name "LVDS1_TX2_P") (class "Default")
      (node (ref "U1") (pin "AB2") (pinfunction "LVDS1_TX2_P_AB2") (pintype "output"))
    )
    (net (code "239") (name "MICROPHONE_DET") (class "Default")
      (node (ref "R597") (pin "2") (pinfunction "2_2") (pintype "passive"))
    )
    (net (code "240") (name "MX6_ONOFF") (class "Default")
      (node (ref "U1") (pin "D12") (pinfunction "ONOFF_D12") (pintype "input"))
    )
    (net (code "241") (name "PCIE_DIS_B") (class "Default")
      (node (ref "R36") (pin "2") (pinfunction "2_2") (pintype "passive"))
    )
    (net (code "242") (name "PCIE_PWR_EN") (class "Default")
      (node (ref "R123") (pin "1") (pinfunction "1_1") (pintype "passive"))
    )
    (net (code "243") (name "PCIE_RST_B") (class "Default")
      (node (ref "R596") (pin "2") (pinfunction "2_2") (pintype "passive"))
    )
    (net (code "244") (name "PCIE_RXM") (class "Default")
      (node (ref "U1") (pin "B1") (pinfunction "PCIE_RXM_B1") (pintype "input"))
    )
    (net (code "245") (name "PCIE_RXP") (class "Default")
      (node (ref "U1") (pin "B2") (pinfunction "PCIE_RXP_B2") (pintype "input"))
    )
    (net (code "246") (name "PCIE_TXM") (class "Default")
      (node (ref "U1") (pin "A3") (pinfunction "PCIE_TXM_A3") (pintype "output"))
    )
    (net (code "247") (name "PCIE_TXP") (class "Default")
      (node (ref "U1") (pin "B3") (pinfunction "PCIE_TXP_B3") (pintype "output"))
    )
    (net (code "248") (name "PCIE_WAKE_B") (class "Default")
      (node (ref "U1") (pin "P3") (pinfunction "CSI0_DATA_EN_P3") (pintype "bidirectional"))
    )
    (net (code "249") (name "PMIC_5V") (class "Default")
      (node (ref "R302") (pin "1") (pinfunction "1_1") (pintype "passive"))
    )
    (net (code "250") (name "PMIC_INT_B") (class "Default")
      (node (ref "U1") (pin "P6") (pinfunction "GPIO_18_P6") (pintype "bidirectional"))
    )
    (net (code "251") (name "PMIC_ON_REQ") (class "Default")
      (node (ref "U1") (pin "D11") (pinfunction "PMIC_ON_REQ_D11") (pintype "output"))
    )
    (net (code "252") (name "PMIC_STBY_REQ") (class "Default")
      (node (ref "U1") (pin "F11") (pinfunction "PMIC_STBY_REQ_F11") (pintype "output"))
    )
    (net (code "253") (name "POR_B") (class "Default")
      (node (ref "U1") (pin "C11") (pinfunction "~{POR}_C11") (pintype "input"))
    )
    (net (code "254") (name "PWR_BTN_SNS") (class "Default")
      (node (ref "U1") (pin "J19") (pinfunction "EIM_D29_J19") (pintype "bidirectional"))
    )
    (net (code "255") (name "RGMII_INT") (class "Default")
      (node (ref "U1") (pin "W22") (pinfunction "ENET_RXD1_W22") (pintype "bidirectional"))
    )
    (net (code "256") (name "RGMII_MDC") (class "Default")
      (node (ref "U1") (pin "V20") (pinfunction "ENET_MDC_V20") (pintype "bidirectional"))
    )
    (net (code "257") (name "RGMII_MDIO") (class "Default")
      (node (ref "U1") (pin "V23") (pinfunction "ENET_MDIO_V23") (pintype "bidirectional"))
    )
    (net (code "258") (name "RGMII_RXCLK") (class "Default")
      (node (ref "U1") (pin "B25") (pinfunction "RGMII_RXC_B25") (pintype "input"))
    )
    (net (code "259") (name "RGMII_RXD0") (class "Default")
      (node (ref "U1") (pin "C24") (pinfunction "RGMII_RD0_C24") (pintype "input"))
    )
    (net (code "260") (name "RGMII_RXD1") (class "Default")
      (node (ref "U1") (pin "B23") (pinfunction "RGMII_RD1_B23") (pintype "input"))
    )
    (net (code "261") (name "RGMII_RXD2") (class "Default")
      (node (ref "U1") (pin "B24") (pinfunction "RGMII_RD2_B24") (pintype "input"))
    )
    (net (code "262") (name "RGMII_RXD3") (class "Default")
      (node (ref "U1") (pin "D23") (pinfunction "RGMII_RD3_D23") (pintype "input"))
    )
    (net (code "263") (name "RGMII_RXDV") (class "Default")
      (node (ref "U1") (pin "D22") (pinfunction "RGMII_RX_CTL_D22") (pintype "input"))
    )
    (net (code "264") (name "RGMII_TXCLK") (class "Default")
      (node (ref "U1") (pin "D21") (pinfunction "RGMII_TXC_D21") (pintype "output"))
    )
    (net (code "265") (name "RGMII_TXD0") (class "Default")
      (node (ref "U1") (pin "C22") (pinfunction "RGMII_TD0_C22") (pintype "output"))
    )
    (net (code "266") (name "RGMII_TXD1") (class "Default")
      (node (ref "U1") (pin "F20") (pinfunction "RGMII_TD1_F20") (pintype "output"))
    )
    (net (code "267") (name "RGMII_TXD2") (class "Default")
      (node (ref "U1") (pin "E21") (pinfunction "RGMII_TD2_E21") (pintype "output"))
    )
    (net (code "268") (name "RGMII_TXD3") (class "Default")
      (node (ref "U1") (pin "A24") (pinfunction "RGMII_TD3_A24") (pintype "output"))
    )
    (net (code "269") (name "RGMII_TXEN") (class "Default")
      (node (ref "U1") (pin "C23") (pinfunction "RGMII_TX_CTL_C23") (pintype "output"))
    )
    (net (code "270") (name "RGMII_nRST") (class "Default")
      (node (ref "U1") (pin "U21") (pinfunction "ENET_CRS_DV_U21") (pintype "bidirectional"))
    )
    (net (code "271") (name "SATA_DEVSLP") (class "Default")
      (node (ref "R676") (pin "2") (pinfunction "2_2") (pintype "passive"))
    )
    (net (code "272") (name "SATA_RXN") (class "Default")
      (node (ref "U1") (pin "A14") (pinfunction "SATA_RXM_A14") (pintype "input"))
    )
    (net (code "273") (name "SATA_RXP") (class "Default")
      (node (ref "U1") (pin "B14") (pinfunction "SATA_RXP_B14") (pintype "input"))
    )
    (net (code "274") (name "SATA_TXN") (class "Default")
      (node (ref "U1") (pin "B12") (pinfunction "SATA_TXM_B12") (pintype "output"))
    )
    (net (code "275") (name "SATA_TXP") (class "Default")
      (node (ref "U1") (pin "A12") (pinfunction "SATA_TXP_A12") (pintype "output"))
    )
    (net (code "276") (name "SD2_CD_B") (class "Default")
      (node (ref "U1") (pin "F16") (pinfunction "NANDF_D2_F16") (pintype "bidirectional"))
    )
    (net (code "277") (name "SD2_CLK") (class "Default")
      (node (ref "U1") (pin "C21") (pinfunction "SD2_CLK_C21") (pintype "bidirectional"))
    )
    (net (code "278") (name "SD2_CMD") (class "Default")
      (node (ref "U1") (pin "F19") (pinfunction "SD2_CMD_F19") (pintype "bidirectional"))
    )
    (net (code "279") (name "SD2_DATA0") (class "Default")
      (node (ref "U1") (pin "A22") (pinfunction "SD2_DAT0_A22") (pintype "bidirectional"))
    )
    (net (code "280") (name "SD2_DATA1") (class "Default")
      (node (ref "U1") (pin "E20") (pinfunction "SD2_DAT1_E20") (pintype "bidirectional"))
    )
    (net (code "281") (name "SD2_DATA2") (class "Default")
      (node (ref "U1") (pin "A23") (pinfunction "SD2_DAT2_A23") (pintype "bidirectional"))
    )
    (net (code "282") (name "SD2_DATA3") (class "Default")
      (node (ref "U1") (pin "B22") (pinfunction "SD2_DAT3_B22") (pintype "bidirectional"))
    )
    (net (code "283") (name "SD2_DATA4") (class "Default")
      (node (ref "U1") (pin "A19") (pinfunction "NANDF_D4_A19") (pintype "bidirectional"))
    )
    (net (code "284") (name "SD2_DATA5") (class "Default")
      (node (ref "U1") (pin "B18") (pinfunction "NANDF_D5_B18") (pintype "bidirectional"))
    )
    (net (code "285") (name "SD2_DATA6") (class "Default")
      (node (ref "U1") (pin "E17") (pinfunction "NANDF_D6_E17") (pintype "bidirectional"))
    )
    (net (code "286") (name "SD2_DATA7") (class "Default")
      (node (ref "U1") (pin "C18") (pinfunction "NANDF_D7_C18") (pintype "bidirectional"))
    )
    (net (code "287") (name "SD2_WP") (class "Default")
      (node (ref "U1") (pin "D17") (pinfunction "NANDF_D3_D17") (pintype "bidirectional"))
    )
    (net (code "288") (name "SD3_CD_B") (class "Default")
      (node (ref "U1") (pin "A18") (pinfunction "NANDF_D0_A18") (pintype "bidirectional"))
    )
    (net (code "289") (name "SD3_CLK") (class "Default")
      (node (ref "U1") (pin "D14") (pinfunction "SD3_CLK_D14") (pintype "bidirectional"))
    )
    (net (code "290") (name "SD3_CMD") (class "Default")
      (node (ref "U1") (pin "B13") (pinfunction "SD3_CMD_B13") (pintype "bidirectional"))
    )
    (net (code "291") (name "SD3_DATA0") (class "Default")
      (node (ref "U1") (pin "E14") (pinfunction "SD3_DAT0_E14") (pintype "bidirectional"))
    )
    (net (code "292") (name "SD3_DATA1") (class "Default")
      (node (ref "U1") (pin "F14") (pinfunction "SD3_DAT1_F14") (pintype "bidirectional"))
    )
    (net (code "293") (name "SD3_DATA2") (class "Default")
      (node (ref "U1") (pin "A15") (pinfunction "SD3_DAT2_A15") (pintype "bidirectional"))
    )
    (net (code "294") (name "SD3_DATA3") (class "Default")
      (node (ref "U1") (pin "B15") (pinfunction "SD3_DAT3_B15") (pintype "bidirectional"))
    )
    (net (code "295") (name "SD3_DATA4") (class "Default")
      (node (ref "U1") (pin "D13") (pinfunction "SD3_DAT4_D13") (pintype "bidirectional"))
    )
    (net (code "296") (name "SD3_DATA5") (class "Default")
      (node (ref "U1") (pin "C13") (pinfunction "SD3_DAT5_C13") (pintype "bidirectional"))
    )
    (net (code "297") (name "SD3_DATA6") (class "Default")
      (node (ref "U1") (pin "E13") (pinfunction "SD3_DAT6_E13") (pintype "bidirectional"))
    )
    (net (code "298") (name "SD3_DATA7") (class "Default")
      (node (ref "U1") (pin "F13") (pinfunction "SD3_DAT7_F13") (pintype "bidirectional"))
    )
    (net (code "299") (name "SD3_WP") (class "Default")
      (node (ref "U1") (pin "C17") (pinfunction "NANDF_D1_C17") (pintype "bidirectional"))
    )
    (net (code "300") (name "SD4_CLK") (class "Default")
      (node (ref "U1") (pin "E16") (pinfunction "SD4_CLK_E16") (pintype "bidirectional"))
    )
    (net (code "301") (name "SD4_CMD") (class "Default")
      (node (ref "U1") (pin "B17") (pinfunction "SD4_CMD_B17") (pintype "bidirectional"))
    )
    (net (code "302") (name "SD4_DATA0") (class "Default")
      (node (ref "U1") (pin "D18") (pinfunction "SD4_DAT0_D18") (pintype "bidirectional"))
    )
    (net (code "303") (name "SD4_DATA1") (class "Default")
      (node (ref "U1") (pin "B19") (pinfunction "SD4_DAT1_B19") (pintype "bidirectional"))
    )
    (net (code "304") (name "SD4_DATA2") (class "Default")
      (node (ref "U1") (pin "F17") (pinfunction "SD4_DAT2_F17") (pintype "bidirectional"))
    )
    (net (code "305") (name "SD4_DATA3") (class "Default")
      (node (ref "U1") (pin "A20") (pinfunction "SD4_DAT3_A20") (pintype "bidirectional"))
    )
    (net (code "306") (name "SD4_DATA4") (class "Default")
      (node (ref "U1") (pin "E18") (pinfunction "SD4_DAT4_E18") (pintype "bidirectional"))
    )
    (net (code "307") (name "SD4_DATA5") (class "Default")
      (node (ref "U1") (pin "C19") (pinfunction "SD4_DAT5_C19") (pintype "bidirectional"))
    )
    (net (code "308") (name "SD4_DATA6") (class "Default")
      (node (ref "U1") (pin "B20") (pinfunction "SD4_DAT6_B20") (pintype "bidirectional"))
    )
    (net (code "309") (name "SD4_DATA7") (class "Default")
      (node (ref "U1") (pin "D19") (pinfunction "SD4_DAT7_D19") (pintype "bidirectional"))
    )
    (net (code "310") (name "SENSOR_PWR_EN") (class "Default")
      (node (ref "R136") (pin "1") (pinfunction "1_1") (pintype "passive"))
    )
    (net (code "311") (name "SPDIF_CLK") (class "Default")
      (node (ref "R114") (pin "1") (pinfunction "1_1") (pintype "passive"))
      (node (ref "U1") (pin "R3") (pinfunction "GPIO_7_R3") (pintype "bidirectional"))
    )
    (net (code "312") (name "SPDIF_OUT") (class "Default")
      (node (ref "R596") (pin "1") (pinfunction "1_1") (pintype "passive"))
      (node (ref "U1") (pin "R1") (pinfunction "GPIO_17_R1") (pintype "bidirectional"))
    )
    (net (code "313") (name "TAMPER") (class "Default")
      (node (ref "U1") (pin "E11") (pinfunction "TAMPER_E11") (pintype "input"))
    )
    (net (code "314") (name "TEST_MODE") (class "Default")
      (node (ref "U1") (pin "E12") (pinfunction "TEST_MODE_E12") (pintype "input"))
    )
    (net (code "315") (name "TS_INT") (class "Default")
      (node (ref "R128") (pin "1") (pinfunction "1_1") (pintype "passive"))
    )
    (net (code "316") (name "UART1_RX") (class "Default")
      (node (ref "U1") (pin "M3") (pinfunction "CSI0_DAT11_M3") (pintype "bidirectional"))
    )
    (net (code "317") (name "UART1_TX") (class "Default")
      (node (ref "U1") (pin "M1") (pinfunction "CSI0_DAT10_M1") (pintype "bidirectional"))
    )
    (net (code "318") (name "UART3_RXD") (class "Default")
      (node (ref "R126") (pin "1") (pinfunction "1_1") (pintype "passive"))
    )
    (net (code "319") (name "UART3_TXD") (class "Default")
      (node (ref "R127") (pin "1") (pinfunction "1_1") (pintype "passive"))
    )
    (net (code "320") (name "UOK_B") (class "Default")
      (node (ref "U1") (pin "W21") (pinfunction "ENET_RXD0_W21") (pintype "bidirectional"))
    )
    (net (code "321") (name "USB_H1_OC") (class "Default")
      (node (ref "R134") (pin "1") (pinfunction "1_1") (pintype "passive"))
    )
    (net (code "322") (name "USB_H1_PWR_EN") (class "Default")
      (node (ref "U1") (pin "W20") (pinfunction "ENET_TXD1_W20") (pintype "bidirectional"))
    )
    (net (code "323") (name "USB_H1_VBUS") (class "Default")
      (node (ref "R301") (pin "1") (pinfunction "1_1") (pintype "passive"))
    )
    (net (code "324") (name "USB_HOST_DN") (class "Default")
      (node (ref "U1") (pin "F10") (pinfunction "USB_H1_DN_F10") (pintype "bidirectional"))
    )
    (net (code "325") (name "USB_HOST_DP") (class "Default")
      (node (ref "U1") (pin "E10") (pinfunction "USB_H1_DP_E10") (pintype "bidirectional"))
    )
    (net (code "326") (name "USB_OTG_DN") (class "Default")
      (node (ref "U1") (pin "B6") (pinfunction "USB_OTG_DN_B6") (pintype "bidirectional"))
    )
    (net (code "327") (name "USB_OTG_DP") (class "Default")
      (node (ref "U1") (pin "A6") (pinfunction "USB_OTG_DP_A6") (pintype "bidirectional"))
    )
    (net (code "328") (name "USB_OTG_ID") (class "Default")
      (node (ref "U1") (pin "W23") (pinfunction "ENET_RX_ER_W23") (pintype "bidirectional"))
    )
    (net (code "329") (name "USB_OTG_OC") (class "Default")
      (node (ref "R125") (pin "1") (pinfunction "1_1") (pintype "passive"))
    )
    (net (code "330") (name "USB_OTG_PWR_EN") (class "Default")
      (node (ref "R137") (pin "1") (pinfunction "1_1") (pintype "passive"))
    )
    (net (code "331") (name "USB_OTG_VBUS") (class "Default")
      (node (ref "C642") (pin "1") (pinfunction "1_1") (pintype "passive"))
      (node (ref "U1") (pin "E9") (pinfunction "USB_OTG_VBUS_E9") (pintype "power_in"))
    )
    (net (code "332") (name "USR_DEF_RED_LED") (class "Default")
      (node (ref "R588") (pin "2") (pinfunction "2_2") (pintype "passive"))
    )
    (net (code "333") (name "VDDSOC_VP") (class "Default")
      (node (ref "L13") (pin "1") (pinfunction "1_1") (pintype "passive"))
      (node (ref "R48") (pin "1") (pinfunction "1_1") (pintype "passive"))
      (node (ref "R49") (pin "1") (pinfunction "1_1") (pintype "passive"))
      (node (ref "R96") (pin "1") (pinfunction "1_1") (pintype "passive"))
    )
    (net (code "334") (name "WDOG_B") (class "Default")
      (node (ref "R300") (pin "2") (pinfunction "2_2") (pintype "passive"))
    )
    (net (code "335") (name "unconnected-(U1B-GPIO_16-PadR2)") (class "Default")
      (node (ref "U1") (pin "R2") (pinfunction "GPIO_16_R2") (pintype "bidirectional"))
    )
    (net (code "336") (name "unconnected-(U1B-MLB_CN-PadA11)") (class "Default")
      (node (ref "U1") (pin "A11") (pinfunction "MLB_CN_A11") (pintype "input"))
    )
    (net (code "337") (name "unconnected-(U1B-MLB_CP-PadB11)") (class "Default")
      (node (ref "U1") (pin "B11") (pinfunction "MLB_CP_B11") (pintype "input"))
    )
    (net (code "338") (name "unconnected-(U1B-MLB_DN-PadB10)") (class "Default")
      (node (ref "U1") (pin "B10") (pinfunction "MLB_DN_B10") (pintype "bidirectional"))
    )
    (net (code "339") (name "unconnected-(U1B-MLB_DP-PadA10)") (class "Default")
      (node (ref "U1") (pin "A10") (pinfunction "MLB_DP_A10") (pintype "bidirectional"))
    )
    (net (code "340") (name "unconnected-(U1B-MLB_SN-PadA9)") (class "Default")
      (node (ref "U1") (pin "A9") (pinfunction "MLB_SN_A9") (pintype "bidirectional"))
    )
    (net (code "341") (name "unconnected-(U1B-MLB_SP-PadB9)") (class "Default")
      (node (ref "U1") (pin "B9") (pinfunction "MLB_SP_B9") (pintype "bidirectional"))
    )
    (net (code "342") (name "unconnected-(U1C-CLK2_N-PadC5)") (class "Default")
      (node (ref "U1") (pin "C5") (pinfunction "CLK2_N_C5") (pintype "bidirectional"))
    )
    (net (code "343") (name "unconnected-(U1C-CLK2_P-PadD5)") (class "Default")
      (node (ref "U1") (pin "D5") (pinfunction "CLK2_P_D5") (pintype "bidirectional"))
    )
    (net (code "344") (name "unconnected-(U1D-CSI_D2M-PadE1)") (class "Default")
      (node (ref "U1") (pin "E1") (pinfunction "CSI_D2M_E1") (pintype "input"))
    )
    (net (code "345") (name "unconnected-(U1D-CSI_D2P-PadE2)") (class "Default")
      (node (ref "U1") (pin "E2") (pinfunction "CSI_D2P_E2") (pintype "input"))
    )
    (net (code "346") (name "unconnected-(U1D-CSI_D3M-PadF2)") (class "Default")
      (node (ref "U1") (pin "F2") (pinfunction "CSI_D3M_F2") (pintype "input"))
    )
    (net (code "347") (name "unconnected-(U1D-CSI_D3P-PadF1)") (class "Default")
      (node (ref "U1") (pin "F1") (pinfunction "CSI_D3P_F1") (pintype "input"))
    )
    (net (code "348") (name "unconnected-(U1G-~{USB_OTG_CHD}-PadB8)") (class "Default")
      (node (ref "U1") (pin "B8") (pinfunction "~{USB_OTG_CHD}_B8") (pintype "output"))
    )
    (net (code "349") (name "unconnected-(U514-NC-Pad5)") (class "Default")
      (node (ref "U514") (pin "5") (pinfunction "NC_5") (pintype "passive"))
    )
  )
)
